# ProPrj_ESP32-CNC_2025-08-15.net
KiCad netlist of a schematic drawn in EasyEDA Pro
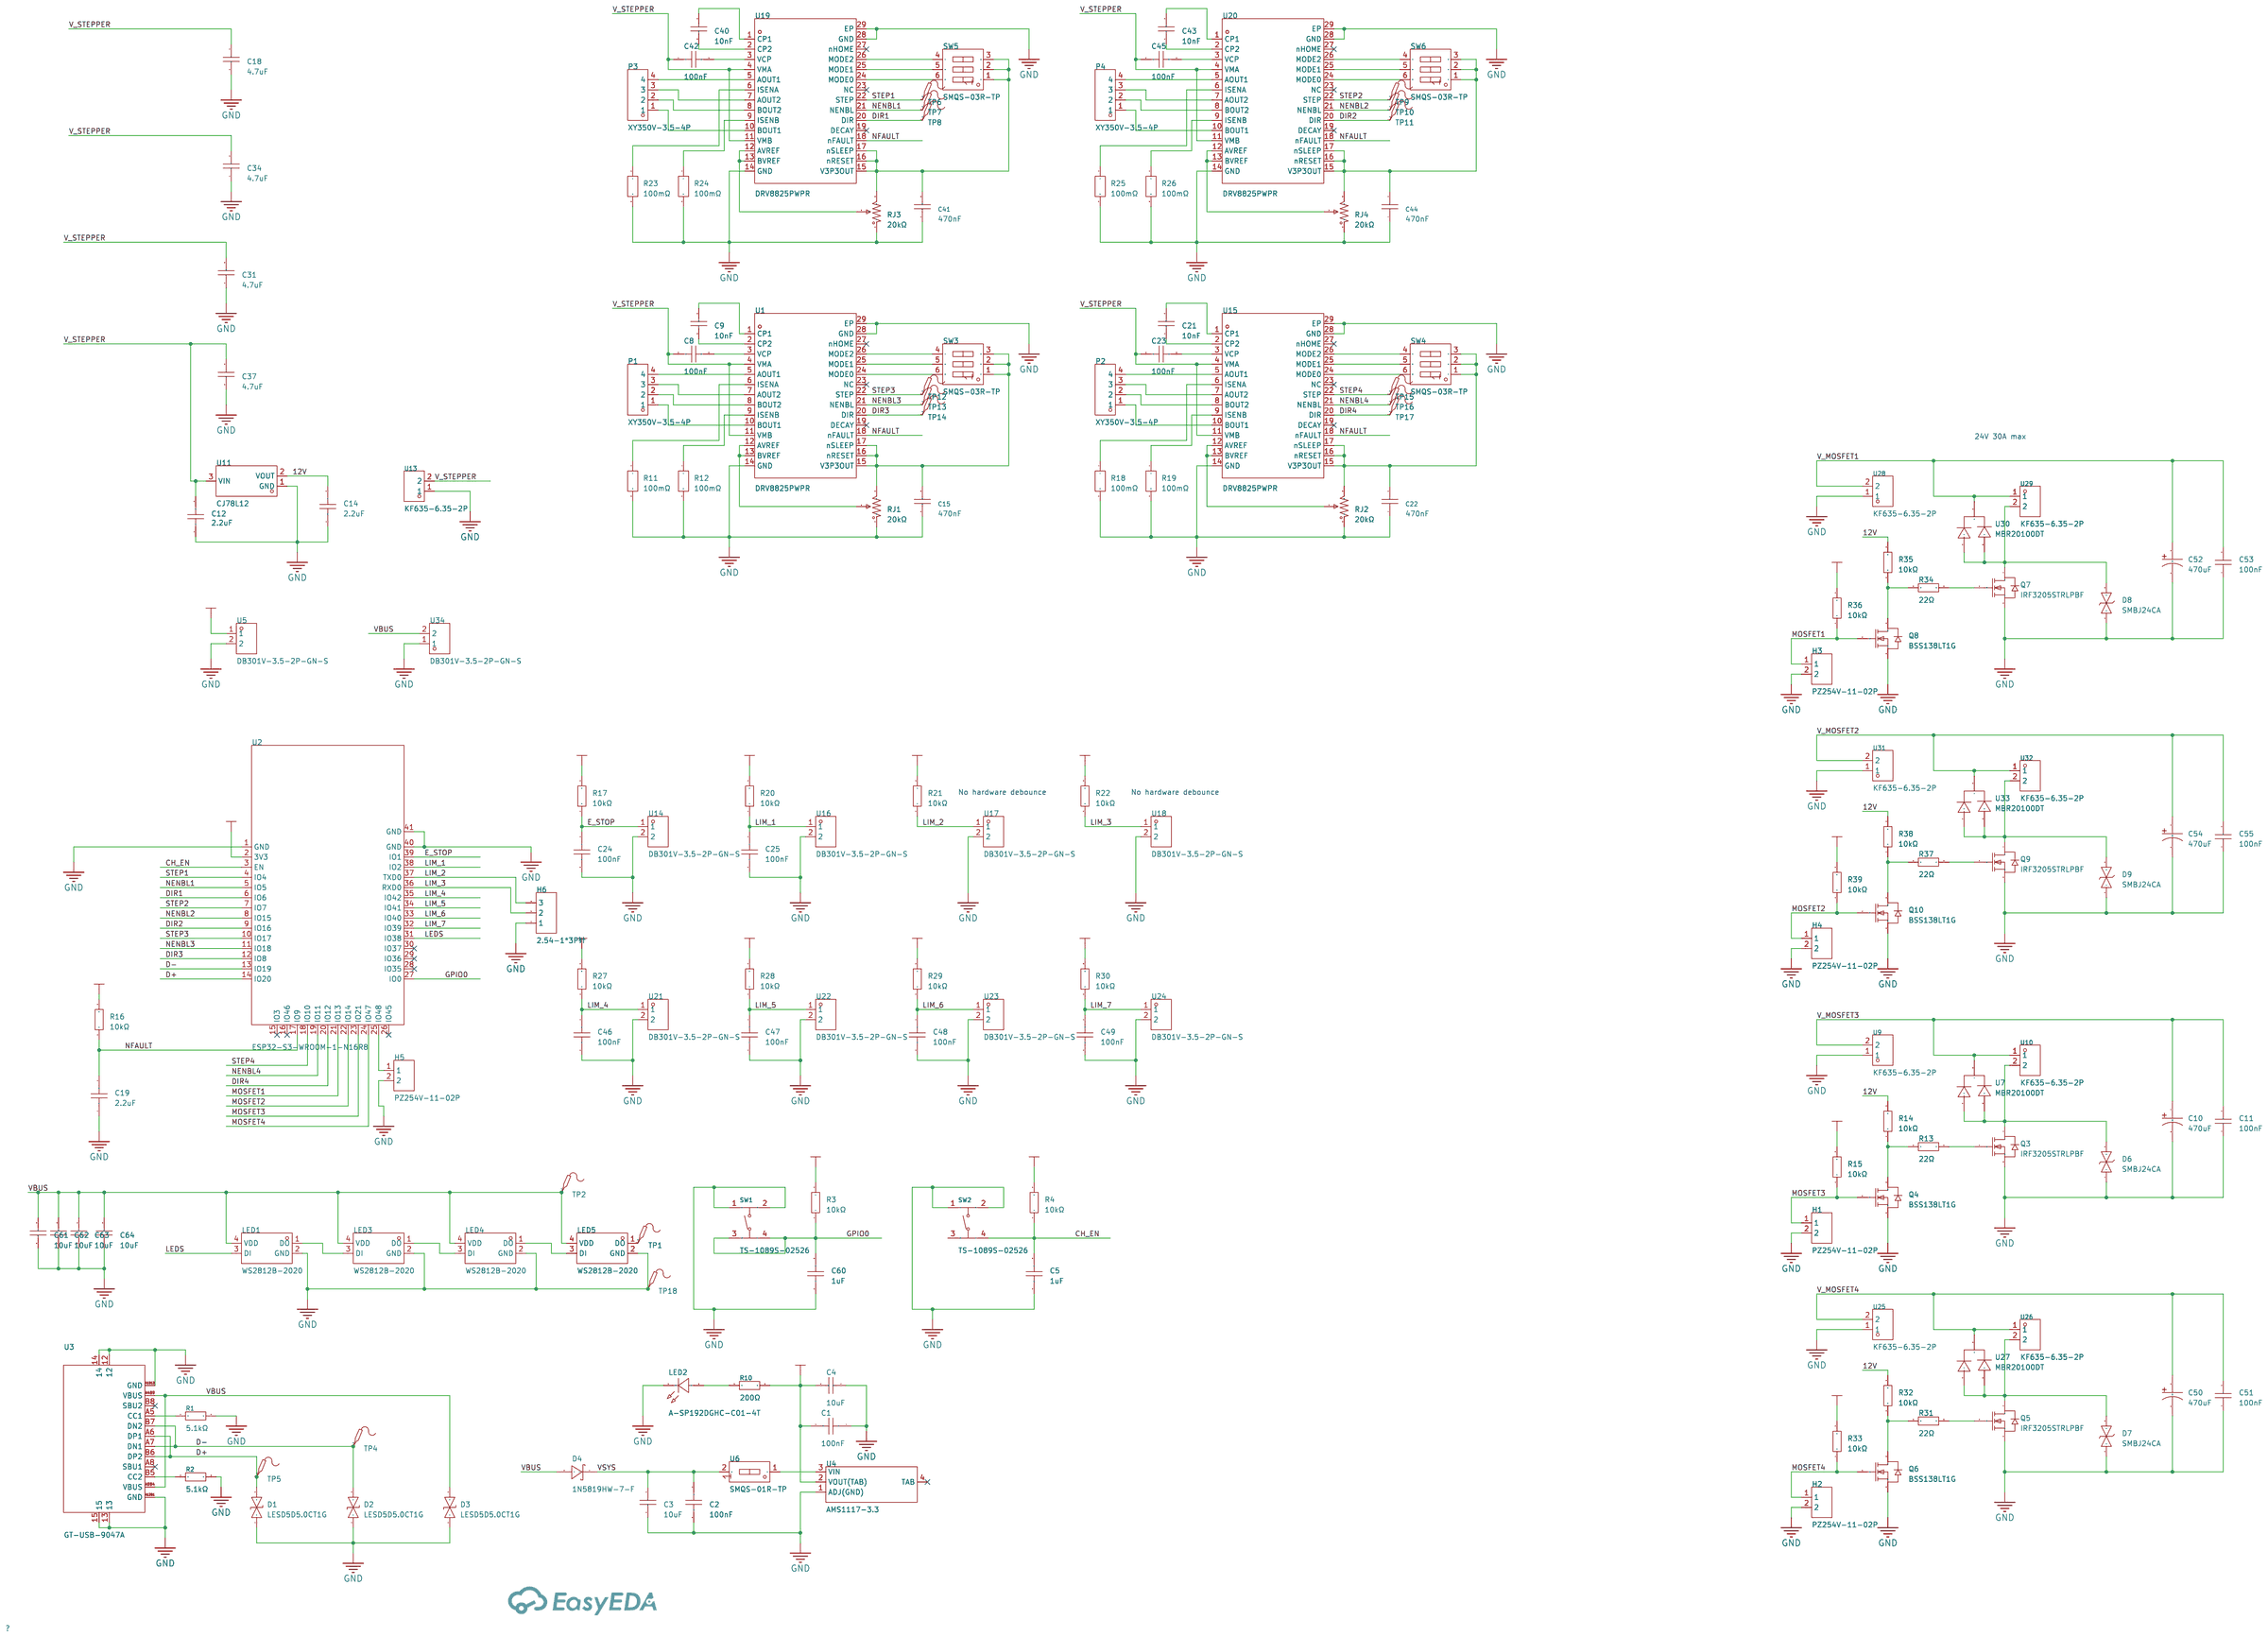
[diagram p0: schematic sheet]

(export (version "E")
  (design (tool "Eeschema 10.0.6"))
  (components
    (comp (ref "C1")
      (value "100nF")
      (footprint "easyedapro:C0402")
      (fields
        (field (name "Manufacturer Part") "CL21B104KCFNNNE")
        (field (name "Manufacturer") "SAMSUNG(三星)")
      )
      (libsource (lib "easyedapro") (part "CL05B104KO5NNNC"))
    )
    (comp (ref "C2")
      (value "100nF")
      (footprint "easyedapro:C0402")
      (fields
        (field (name "Manufacturer Part") "CL21B104KCFNNNE")
        (field (name "Manufacturer") "SAMSUNG(三星)")
      )
      (libsource (lib "easyedapro") (part "CL05B104KO5NNNC"))
    )
    (comp (ref "C3")
      (value "10uF")
      (footprint "easyedapro:C0402")
      (fields
        (field (name "Manufacturer Part") "CL05A106MQ5NUNC")
        (field (name "Manufacturer") "SAMSUNG(三星)")
      )
      (libsource (lib "easyedapro") (part "CL05A106MQ5NUNC"))
    )
    (comp (ref "C4")
      (value "10uF")
      (footprint "easyedapro:C0402")
      (fields
        (field (name "Manufacturer Part") "CL05A106MQ5NUNC")
        (field (name "Manufacturer") "SAMSUNG(三星)")
      )
      (libsource (lib "easyedapro") (part "CL05A106MQ5NUNC"))
    )
    (comp (ref "C5")
      (value "1uF")
      (footprint "easyedapro:C0402")
      (fields
        (field (name "Manufacturer Part") "CL05A105KA5NQNC")
        (field (name "Manufacturer") "SAMSUNG(三星)")
      )
      (libsource (lib "easyedapro") (part "CL05A105KA5NQNC"))
    )
    (comp (ref "C8")
      (value "100nF")
      (footprint "easyedapro:C0603")
      (fields
        (field (name "Manufacturer Part") "CL21B104KCFNNNE")
        (field (name "Manufacturer") "SAMSUNG(三星)")
      )
      (libsource (lib "easyedapro") (part "CC0603KRX7R9BB104"))
    )
    (comp (ref "C9")
      (value "10nF")
      (footprint "easyedapro:C0805")
      (fields
        (field (name "Manufacturer Part") "CL21B103KBANNNC")
        (field (name "Manufacturer") "SAMSUNG(三星)")
      )
      (libsource (lib "easyedapro") (part "CL21B103KBANNNC"))
    )
    (comp (ref "C10")
      (value "470uF")
      (footprint "easyedapro:CAP-SMD_BD12.5-L13.0-W13.0-RD")
      (fields (field (name "Manufacturer Part") "RVT1H471M1213") (field (name "Manufacturer") "ROQANG(容强)"))
      (libsource (lib "easyedapro") (part "RVT1H471M1213"))
    )
    (comp (ref "C11")
      (value "100nF")
      (footprint "easyedapro:C0805")
      (fields
        (field (name "Manufacturer Part") "CL21B104KCFNNNE")
        (field (name "Manufacturer") "SAMSUNG(三星)")
      )
      (libsource (lib "easyedapro") (part "CL21B104KCFNNNE"))
    )
    (comp (ref "C12")
      (value "2.2uF")
      (footprint "easyedapro:C0805")
      (fields
        (field (name "Manufacturer Part") "CL21A225KBQNNNE")
        (field (name "Manufacturer") "SAMSUNG(三星)")
      )
      (libsource (lib "easyedapro") (part "CL21A225KBQNNNE"))
    )
    (comp (ref "C14")
      (value "2.2uF")
      (footprint "easyedapro:C0805")
      (fields
        (field (name "Manufacturer Part") "CL21A225KBQNNNE")
        (field (name "Manufacturer") "SAMSUNG(三星)")
      )
      (libsource (lib "easyedapro") (part "CL21A225KBQNNNE"))
    )
    (comp (ref "C15")
      (value "470nF")
      (footprint "easyedapro:C0805")
      (fields
        (field (name "Manufacturer Part") "CL21B474KBFNNNE")
        (field (name "Manufacturer") "SAMSUNG(三星)")
      )
      (libsource (lib "easyedapro") (part "CL21B474KBFNNNE"))
    )
    (comp (ref "C18")
      (value "4.7uF")
      (footprint "easyedapro:C1206")
      (description "Capacitance:4.7uF Tolerance:±10% Tolerance:±10% Voltage Rating:50V Temperature Coefficient:X7R")
      (fields (field (name "Manufacturer Part") "1206B475K500NT") (field (name "Manufacturer") "FH(风华)"))
      (libsource (lib "easyedapro") (part "1206B475K500NT"))
    )
    (comp (ref "C19")
      (value "2.2uF")
      (footprint "easyedapro:C0805")
      (fields
        (field (name "Manufacturer Part") "CL21A225KBQNNNE")
        (field (name "Manufacturer") "SAMSUNG(三星)")
      )
      (libsource (lib "easyedapro") (part "CL21A225KBQNNNE"))
    )
    (comp (ref "C21")
      (value "10nF")
      (footprint "easyedapro:C0805")
      (fields
        (field (name "Manufacturer Part") "CL21B103KBANNNC")
        (field (name "Manufacturer") "SAMSUNG(三星)")
      )
      (libsource (lib "easyedapro") (part "CL21B103KBANNNC"))
    )
    (comp (ref "C22")
      (value "470nF")
      (footprint "easyedapro:C0805")
      (fields
        (field (name "Manufacturer Part") "CL21B474KBFNNNE")
        (field (name "Manufacturer") "SAMSUNG(三星)")
      )
      (libsource (lib "easyedapro") (part "CL21B474KBFNNNE"))
    )
    (comp (ref "C23")
      (value "100nF")
      (footprint "easyedapro:C0603")
      (fields
        (field (name "Manufacturer Part") "CL21B104KCFNNNE")
        (field (name "Manufacturer") "SAMSUNG(三星)")
      )
      (libsource (lib "easyedapro") (part "CC0603KRX7R9BB104"))
    )
    (comp (ref "C24")
      (value "100nF")
      (footprint "easyedapro:C0402")
      (fields
        (field (name "Manufacturer Part") "CL21B104KCFNNNE")
        (field (name "Manufacturer") "SAMSUNG(三星)")
      )
      (libsource (lib "easyedapro") (part "CL05B104KO5NNNC"))
    )
    (comp (ref "C25")
      (value "100nF")
      (footprint "easyedapro:C0402")
      (fields
        (field (name "Manufacturer Part") "CL21B104KCFNNNE")
        (field (name "Manufacturer") "SAMSUNG(三星)")
      )
      (libsource (lib "easyedapro") (part "CL05B104KO5NNNC"))
    )
    (comp (ref "C31")
      (value "4.7uF")
      (footprint "easyedapro:C1206")
      (description "Capacitance:4.7uF Tolerance:±10% Tolerance:±10% Voltage Rating:50V Temperature Coefficient:X7R")
      (fields (field (name "Manufacturer Part") "1206B475K500NT") (field (name "Manufacturer") "FH(风华)"))
      (libsource (lib "easyedapro") (part "1206B475K500NT"))
    )
    (comp (ref "C34")
      (value "4.7uF")
      (footprint "easyedapro:C1206")
      (description "Capacitance:4.7uF Tolerance:±10% Tolerance:±10% Voltage Rating:50V Temperature Coefficient:X7R")
      (fields (field (name "Manufacturer Part") "1206B475K500NT") (field (name "Manufacturer") "FH(风华)"))
      (libsource (lib "easyedapro") (part "1206B475K500NT"))
    )
    (comp (ref "C37")
      (value "4.7uF")
      (footprint "easyedapro:C1206")
      (description "Capacitance:4.7uF Tolerance:±10% Tolerance:±10% Voltage Rating:50V Temperature Coefficient:X7R")
      (fields (field (name "Manufacturer Part") "1206B475K500NT") (field (name "Manufacturer") "FH(风华)"))
      (libsource (lib "easyedapro") (part "1206B475K500NT"))
    )
    (comp (ref "C40")
      (value "10nF")
      (footprint "easyedapro:C0805")
      (fields
        (field (name "Manufacturer Part") "CL21B103KBANNNC")
        (field (name "Manufacturer") "SAMSUNG(三星)")
      )
      (libsource (lib "easyedapro") (part "CL21B103KBANNNC"))
    )
    (comp (ref "C41")
      (value "470nF")
      (footprint "easyedapro:C0805")
      (fields
        (field (name "Manufacturer Part") "CL21B474KBFNNNE")
        (field (name "Manufacturer") "SAMSUNG(三星)")
      )
      (libsource (lib "easyedapro") (part "CL21B474KBFNNNE"))
    )
    (comp (ref "C42")
      (value "100nF")
      (footprint "easyedapro:C0603")
      (fields
        (field (name "Manufacturer Part") "CL21B104KCFNNNE")
        (field (name "Manufacturer") "SAMSUNG(三星)")
      )
      (libsource (lib "easyedapro") (part "CC0603KRX7R9BB104"))
    )
    (comp (ref "C43")
      (value "10nF")
      (footprint "easyedapro:C0805")
      (fields
        (field (name "Manufacturer Part") "CL21B103KBANNNC")
        (field (name "Manufacturer") "SAMSUNG(三星)")
      )
      (libsource (lib "easyedapro") (part "CL21B103KBANNNC"))
    )
    (comp (ref "C44")
      (value "470nF")
      (footprint "easyedapro:C0805")
      (fields
        (field (name "Manufacturer Part") "CL21B474KBFNNNE")
        (field (name "Manufacturer") "SAMSUNG(三星)")
      )
      (libsource (lib "easyedapro") (part "CL21B474KBFNNNE"))
    )
    (comp (ref "C45")
      (value "100nF")
      (footprint "easyedapro:C0603")
      (fields
        (field (name "Manufacturer Part") "CL21B104KCFNNNE")
        (field (name "Manufacturer") "SAMSUNG(三星)")
      )
      (libsource (lib "easyedapro") (part "CC0603KRX7R9BB104"))
    )
    (comp (ref "C46")
      (value "100nF")
      (footprint "easyedapro:C0402")
      (fields
        (field (name "Manufacturer Part") "CL21B104KCFNNNE")
        (field (name "Manufacturer") "SAMSUNG(三星)")
      )
      (libsource (lib "easyedapro") (part "CL05B104KO5NNNC"))
    )
    (comp (ref "C47")
      (value "100nF")
      (footprint "easyedapro:C0402")
      (fields
        (field (name "Manufacturer Part") "CL21B104KCFNNNE")
        (field (name "Manufacturer") "SAMSUNG(三星)")
      )
      (libsource (lib "easyedapro") (part "CL05B104KO5NNNC"))
    )
    (comp (ref "C48")
      (value "100nF")
      (footprint "easyedapro:C0402")
      (fields
        (field (name "Manufacturer Part") "CL21B104KCFNNNE")
        (field (name "Manufacturer") "SAMSUNG(三星)")
      )
      (libsource (lib "easyedapro") (part "CL05B104KO5NNNC"))
    )
    (comp (ref "C49")
      (value "100nF")
      (footprint "easyedapro:C0402")
      (fields
        (field (name "Manufacturer Part") "CL21B104KCFNNNE")
        (field (name "Manufacturer") "SAMSUNG(三星)")
      )
      (libsource (lib "easyedapro") (part "CL05B104KO5NNNC"))
    )
    (comp (ref "C50")
      (value "470uF")
      (footprint "easyedapro:CAP-SMD_BD12.5-L13.0-W13.0-RD")
      (fields (field (name "Manufacturer Part") "RVT1H471M1213") (field (name "Manufacturer") "ROQANG(容强)"))
      (libsource (lib "easyedapro") (part "RVT1H471M1213"))
    )
    (comp (ref "C51")
      (value "100nF")
      (footprint "easyedapro:C0805")
      (fields
        (field (name "Manufacturer Part") "CL21B104KCFNNNE")
        (field (name "Manufacturer") "SAMSUNG(三星)")
      )
      (libsource (lib "easyedapro") (part "CL21B104KCFNNNE"))
    )
    (comp (ref "C52")
      (value "470uF")
      (footprint "easyedapro:CAP-SMD_BD12.5-L13.0-W13.0-RD")
      (fields (field (name "Manufacturer Part") "RVT1H471M1213") (field (name "Manufacturer") "ROQANG(容强)"))
      (libsource (lib "easyedapro") (part "RVT1H471M1213"))
    )
    (comp (ref "C53")
      (value "100nF")
      (footprint "easyedapro:C0805")
      (fields
        (field (name "Manufacturer Part") "CL21B104KCFNNNE")
        (field (name "Manufacturer") "SAMSUNG(三星)")
      )
      (libsource (lib "easyedapro") (part "CL21B104KCFNNNE"))
    )
    (comp (ref "C54")
      (value "470uF")
      (footprint "easyedapro:CAP-SMD_BD12.5-L13.0-W13.0-RD")
      (fields (field (name "Manufacturer Part") "RVT1H471M1213") (field (name "Manufacturer") "ROQANG(容强)"))
      (libsource (lib "easyedapro") (part "RVT1H471M1213"))
    )
    (comp (ref "C55")
      (value "100nF")
      (footprint "easyedapro:C0805")
      (fields
        (field (name "Manufacturer Part") "CL21B104KCFNNNE")
        (field (name "Manufacturer") "SAMSUNG(三星)")
      )
      (libsource (lib "easyedapro") (part "CL21B104KCFNNNE"))
    )
    (comp (ref "C60")
      (value "1uF")
      (footprint "easyedapro:C0402")
      (fields
        (field (name "Manufacturer Part") "CL05A105KA5NQNC")
        (field (name "Manufacturer") "SAMSUNG(三星)")
      )
      (libsource (lib "easyedapro") (part "CL05A105KA5NQNC"))
    )
    (comp (ref "C61")
      (value "10uF")
      (footprint "easyedapro:C0402")
      (fields
        (field (name "Manufacturer Part") "CL05A106MQ5NUNC")
        (field (name "Manufacturer") "SAMSUNG(三星)")
      )
      (libsource (lib "easyedapro") (part "CL05A106MQ5NUNC"))
    )
    (comp (ref "C62")
      (value "10uF")
      (footprint "easyedapro:C0402")
      (fields
        (field (name "Manufacturer Part") "CL05A106MQ5NUNC")
        (field (name "Manufacturer") "SAMSUNG(三星)")
      )
      (libsource (lib "easyedapro") (part "CL05A106MQ5NUNC"))
    )
    (comp (ref "C63")
      (value "10uF")
      (footprint "easyedapro:C0402")
      (fields
        (field (name "Manufacturer Part") "CL05A106MQ5NUNC")
        (field (name "Manufacturer") "SAMSUNG(三星)")
      )
      (libsource (lib "easyedapro") (part "CL05A106MQ5NUNC"))
    )
    (comp (ref "C64")
      (value "10uF")
      (footprint "easyedapro:C0402")
      (fields
        (field (name "Manufacturer Part") "CL05A106MQ5NUNC")
        (field (name "Manufacturer") "SAMSUNG(三星)")
      )
      (libsource (lib "easyedapro") (part "CL05A106MQ5NUNC"))
    )
    (comp (ref "D1")
      (value "LESD5D5.0CT1G")
      (footprint "easyedapro:SOD-523_L1.2-W0.8-LS1.6-BI")
      (fields (field (name "Manufacturer") "LRC(乐山无线电)"))
      (libsource (lib "easyedapro") (part "LESD5D5.0CT1G"))
    )
    (comp (ref "D2")
      (value "LESD5D5.0CT1G")
      (footprint "easyedapro:SOD-523_L1.2-W0.8-LS1.6-BI")
      (fields (field (name "Manufacturer") "LRC(乐山无线电)"))
      (libsource (lib "easyedapro") (part "LESD5D5.0CT1G"))
    )
    (comp (ref "D3")
      (value "LESD5D5.0CT1G")
      (footprint "easyedapro:SOD-523_L1.2-W0.8-LS1.6-BI")
      (fields (field (name "Manufacturer") "LRC(乐山无线电)"))
      (libsource (lib "easyedapro") (part "LESD5D5.0CT1G"))
    )
    (comp (ref "D4")
      (value "1N5819HW-7-F")
      (footprint "easyedapro:SOD-123_L2.7-W1.6-LS3.7-RD")
      (fields (field (name "Manufacturer") "DIODES(美台)"))
      (libsource (lib "easyedapro") (part "1N5819HW-7-F"))
    )
    (comp (ref "D6")
      (value "SMBJ24CA")
      (footprint "easyedapro:SMBG_L4.3-W3.6-LS6.2-BI")
      (fields (field (name "Manufacturer") "JUXING(钜兴)"))
      (libsource (lib "easyedapro") (part "SMBJ24CA_C19634091"))
    )
    (comp (ref "D7")
      (value "SMBJ24CA")
      (footprint "easyedapro:SMBG_L4.3-W3.6-LS6.2-BI")
      (fields (field (name "Manufacturer") "JUXING(钜兴)"))
      (libsource (lib "easyedapro") (part "SMBJ24CA_C19634091"))
    )
    (comp (ref "D8")
      (value "SMBJ24CA")
      (footprint "easyedapro:SMBG_L4.3-W3.6-LS6.2-BI")
      (fields (field (name "Manufacturer") "JUXING(钜兴)"))
      (libsource (lib "easyedapro") (part "SMBJ24CA_C19634091"))
    )
    (comp (ref "D9")
      (value "SMBJ24CA")
      (footprint "easyedapro:SMBG_L4.3-W3.6-LS6.2-BI")
      (fields (field (name "Manufacturer") "JUXING(钜兴)"))
      (libsource (lib "easyedapro") (part "SMBJ24CA_C19634091"))
    )
    (comp (ref "H1")
      (value "PZ254V-11-02P")
      (footprint "easyedapro:HDR-TH_2P-P2.54-V-M")
      (fields (field (name "Manufacturer") "XFCN(兴飞)"))
      (libsource (lib "easyedapro") (part "PZ254V-11-02P"))
    )
    (comp (ref "H2")
      (value "PZ254V-11-02P")
      (footprint "easyedapro:HDR-TH_2P-P2.54-V-M")
      (fields (field (name "Manufacturer") "XFCN(兴飞)"))
      (libsource (lib "easyedapro") (part "PZ254V-11-02P"))
    )
    (comp (ref "H3")
      (value "PZ254V-11-02P")
      (footprint "easyedapro:HDR-TH_2P-P2.54-V-M")
      (fields (field (name "Manufacturer") "XFCN(兴飞)"))
      (libsource (lib "easyedapro") (part "PZ254V-11-02P"))
    )
    (comp (ref "H4")
      (value "PZ254V-11-02P")
      (footprint "easyedapro:HDR-TH_2P-P2.54-V-M")
      (fields (field (name "Manufacturer") "XFCN(兴飞)"))
      (libsource (lib "easyedapro") (part "PZ254V-11-02P"))
    )
    (comp (ref "H5")
      (value "PZ254V-11-02P")
      (footprint "easyedapro:HDR-TH_2P-P2.54-V-M")
      (fields (field (name "Manufacturer") "XFCN(兴飞)"))
      (libsource (lib "easyedapro") (part "PZ254V-11-02P"))
    )
    (comp (ref "H6")
      (value "2.54-1*3P针")
      (footprint "easyedapro:HDR-TH_3P-P2.54-V-M-1")
      (fields (field (name "Manufacturer") "BOOMELE(博穆精密)"))
      (libsource (lib "easyedapro") (part "Header-Male-2.54_1x3"))
    )
    (comp (ref "LED1")
      (value "WS2812B-2020")
      (footprint "easyedapro:LED-SMD_4P-L2.0-W2.0-TL_WS2812B-2020")
      (fields (field (name "Manufacturer") "worldsemi"))
      (libsource (lib "easyedapro") (part "WS2812B-2020"))
    )
    (comp (ref "LED2")
      (value "A-SP192DGHC-C01-4T")
      (footprint "easyedapro:LED0603-FD")
      (fields (field (name "Manufacturer") "Amicc(欧密格光电)"))
      (libsource (lib "easyedapro") (part "A-SP192DGHC-C01-4T"))
    )
    (comp (ref "LED3")
      (value "WS2812B-2020")
      (footprint "easyedapro:LED-SMD_4P-L2.0-W2.0-TL_WS2812B-2020")
      (fields (field (name "Manufacturer") "worldsemi"))
      (libsource (lib "easyedapro") (part "WS2812B-2020"))
    )
    (comp (ref "LED4")
      (value "WS2812B-2020")
      (footprint "easyedapro:LED-SMD_4P-L2.0-W2.0-TL_WS2812B-2020")
      (fields (field (name "Manufacturer") "worldsemi"))
      (libsource (lib "easyedapro") (part "WS2812B-2020"))
    )
    (comp (ref "LED5")
      (value "WS2812B-2020")
      (footprint "easyedapro:LED-SMD_4P-L2.0-W2.0-TL_WS2812B-2020")
      (fields (field (name "Manufacturer") "worldsemi"))
      (libsource (lib "easyedapro") (part "WS2812B-2020"))
    )
    (comp (ref "P1")
      (value "XY350V-3.5-4P")
      (footprint "easyedapro:CONN-TH_XY350V-3.5-4P")
      (fields (field (name "Manufacturer") "XINLAIYA(新莱亚)"))
      (libsource (lib "easyedapro") (part "XY350V-3.5-4P"))
    )
    (comp (ref "P2")
      (value "XY350V-3.5-4P")
      (footprint "easyedapro:CONN-TH_XY350V-3.5-4P")
      (fields (field (name "Manufacturer") "XINLAIYA(新莱亚)"))
      (libsource (lib "easyedapro") (part "XY350V-3.5-4P"))
    )
    (comp (ref "P3")
      (value "XY350V-3.5-4P")
      (footprint "easyedapro:CONN-TH_XY350V-3.5-4P")
      (fields (field (name "Manufacturer") "XINLAIYA(新莱亚)"))
      (libsource (lib "easyedapro") (part "XY350V-3.5-4P"))
    )
    (comp (ref "P4")
      (value "XY350V-3.5-4P")
      (footprint "easyedapro:CONN-TH_XY350V-3.5-4P")
      (fields (field (name "Manufacturer") "XINLAIYA(新莱亚)"))
      (libsource (lib "easyedapro") (part "XY350V-3.5-4P"))
    )
    (comp (ref "Q3")
      (value "IRF3205STRLPBF")
      (footprint "easyedapro:TO-263-2_L10.0-W9.1-P5.08-LS15.2-TL")
      (fields (field (name "Manufacturer") "Infineon(英飞凌)"))
      (libsource (lib "easyedapro") (part "IRF3205STRLPBF"))
    )
    (comp (ref "Q4")
      (value "BSS138LT1G")
      (footprint "easyedapro:SOT-23-3_L2.9-W1.6-P1.90-LS2.8-BR")
      (fields (field (name "Manufacturer") "onsemi(安森美)"))
      (libsource (lib "easyedapro") (part "BSS138LT1G"))
    )
    (comp (ref "Q5")
      (value "IRF3205STRLPBF")
      (footprint "easyedapro:TO-263-2_L10.0-W9.1-P5.08-LS15.2-TL")
      (fields (field (name "Manufacturer") "Infineon(英飞凌)"))
      (libsource (lib "easyedapro") (part "IRF3205STRLPBF"))
    )
    (comp (ref "Q6")
      (value "BSS138LT1G")
      (footprint "easyedapro:SOT-23-3_L2.9-W1.6-P1.90-LS2.8-BR")
      (fields (field (name "Manufacturer") "onsemi(安森美)"))
      (libsource (lib "easyedapro") (part "BSS138LT1G"))
    )
    (comp (ref "Q7")
      (value "IRF3205STRLPBF")
      (footprint "easyedapro:TO-263-2_L10.0-W9.1-P5.08-LS15.2-TL")
      (fields (field (name "Manufacturer") "Infineon(英飞凌)"))
      (libsource (lib "easyedapro") (part "IRF3205STRLPBF"))
    )
    (comp (ref "Q8")
      (value "BSS138LT1G")
      (footprint "easyedapro:SOT-23-3_L2.9-W1.6-P1.90-LS2.8-BR")
      (fields (field (name "Manufacturer") "onsemi(安森美)"))
      (libsource (lib "easyedapro") (part "BSS138LT1G"))
    )
    (comp (ref "Q9")
      (value "IRF3205STRLPBF")
      (footprint "easyedapro:TO-263-2_L10.0-W9.1-P5.08-LS15.2-TL")
      (fields (field (name "Manufacturer") "Infineon(英飞凌)"))
      (libsource (lib "easyedapro") (part "IRF3205STRLPBF"))
    )
    (comp (ref "Q10")
      (value "BSS138LT1G")
      (footprint "easyedapro:SOT-23-3_L2.9-W1.6-P1.90-LS2.8-BR")
      (fields (field (name "Manufacturer") "onsemi(安森美)"))
      (libsource (lib "easyedapro") (part "BSS138LT1G"))
    )
    (comp (ref "R1")
      (value "5.1kΩ")
      (footprint "easyedapro:R0402")
      (fields
        (field (name "Manufacturer Part") "0402WGF5101TCE")
        (field (name "Manufacturer") "UNI-ROYAL(厚声)")
      )
      (libsource (lib "easyedapro") (part "0402WGF5101TCE"))
    )
    (comp (ref "R2")
      (value "5.1kΩ")
      (footprint "easyedapro:R0402")
      (fields
        (field (name "Manufacturer Part") "0402WGF5101TCE")
        (field (name "Manufacturer") "UNI-ROYAL(厚声)")
      )
      (libsource (lib "easyedapro") (part "0402WGF5101TCE"))
    )
    (comp (ref "R3")
      (value "10kΩ")
      (footprint "easyedapro:R0402")
      (fields
        (field (name "Manufacturer Part") "0402WGF1002TCE")
        (field (name "Manufacturer") "UNI-ROYAL(厚声)")
      )
      (libsource (lib "easyedapro") (part "0402WGF1002TCE"))
    )
    (comp (ref "R4")
      (value "10kΩ")
      (footprint "easyedapro:R0402")
      (fields
        (field (name "Manufacturer Part") "0402WGF1002TCE")
        (field (name "Manufacturer") "UNI-ROYAL(厚声)")
      )
      (libsource (lib "easyedapro") (part "0402WGF1002TCE"))
    )
    (comp (ref "R10")
      (value "200Ω")
      (footprint "easyedapro:R0402")
      (fields
        (field (name "Manufacturer Part") "0402WGF2000TCE")
        (field (name "Manufacturer") "UNI-ROYAL(厚声)")
      )
      (libsource (lib "easyedapro") (part "0402WGF2000TCE"))
    )
    (comp (ref "R11")
      (value "100mΩ")
      (footprint "easyedapro:R1206")
      (fields
        (field (name "Manufacturer Part") "HoYH1206-1W-100mR-1%")
        (field (name "Manufacturer") "Milliohm(毫欧)")
      )
      (libsource (lib "easyedapro") (part "HOYH1206-1W-100MR-1%"))
    )
    (comp (ref "R12")
      (value "100mΩ")
      (footprint "easyedapro:R1206")
      (fields
        (field (name "Manufacturer Part") "HoYH1206-1W-100mR-1%")
        (field (name "Manufacturer") "Milliohm(毫欧)")
      )
      (libsource (lib "easyedapro") (part "HOYH1206-1W-100MR-1%"))
    )
    (comp (ref "R13")
      (value "22Ω")
      (footprint "easyedapro:R0603")
      (fields
        (field (name "Manufacturer Part") "0603WAF220JT5E")
        (field (name "Manufacturer") "UNI-ROYAL(厚声)")
      )
      (libsource (lib "easyedapro") (part "0603WAF220JT5E"))
    )
    (comp (ref "R14")
      (value "10kΩ")
      (footprint "easyedapro:R0402")
      (fields
        (field (name "Manufacturer Part") "0402WGF1002TCE")
        (field (name "Manufacturer") "UNI-ROYAL(厚声)")
      )
      (libsource (lib "easyedapro") (part "0402WGF1002TCE"))
    )
    (comp (ref "R15")
      (value "10kΩ")
      (footprint "easyedapro:R0402")
      (fields
        (field (name "Manufacturer Part") "0402WGF1002TCE")
        (field (name "Manufacturer") "UNI-ROYAL(厚声)")
      )
      (libsource (lib "easyedapro") (part "0402WGF1002TCE"))
    )
    (comp (ref "R16")
      (value "10kΩ")
      (footprint "easyedapro:R0402")
      (fields
        (field (name "Manufacturer Part") "0402WGF1002TCE")
        (field (name "Manufacturer") "UNI-ROYAL(厚声)")
      )
      (libsource (lib "easyedapro") (part "0402WGF1002TCE"))
    )
    (comp (ref "R17")
      (value "10kΩ")
      (footprint "easyedapro:R0402")
      (fields
        (field (name "Manufacturer Part") "0402WGF1002TCE")
        (field (name "Manufacturer") "UNI-ROYAL(厚声)")
      )
      (libsource (lib "easyedapro") (part "0402WGF1002TCE"))
    )
    (comp (ref "R18")
      (value "100mΩ")
      (footprint "easyedapro:R1206")
      (fields
        (field (name "Manufacturer Part") "HoYH1206-1W-100mR-1%")
        (field (name "Manufacturer") "Milliohm(毫欧)")
      )
      (libsource (lib "easyedapro") (part "HOYH1206-1W-100MR-1%"))
    )
    (comp (ref "R19")
      (value "100mΩ")
      (footprint "easyedapro:R1206")
      (fields
        (field (name "Manufacturer Part") "HoYH1206-1W-100mR-1%")
        (field (name "Manufacturer") "Milliohm(毫欧)")
      )
      (libsource (lib "easyedapro") (part "HOYH1206-1W-100MR-1%"))
    )
    (comp (ref "R20")
      (value "10kΩ")
      (footprint "easyedapro:R0402")
      (fields
        (field (name "Manufacturer Part") "0402WGF1002TCE")
        (field (name "Manufacturer") "UNI-ROYAL(厚声)")
      )
      (libsource (lib "easyedapro") (part "0402WGF1002TCE"))
    )
    (comp (ref "R21")
      (value "10kΩ")
      (footprint "easyedapro:R0402")
      (fields
        (field (name "Manufacturer Part") "0402WGF1002TCE")
        (field (name "Manufacturer") "UNI-ROYAL(厚声)")
      )
      (libsource (lib "easyedapro") (part "0402WGF1002TCE"))
    )
    (comp (ref "R22")
      (value "10kΩ")
      (footprint "easyedapro:R0402")
      (fields
        (field (name "Manufacturer Part") "0402WGF1002TCE")
        (field (name "Manufacturer") "UNI-ROYAL(厚声)")
      )
      (libsource (lib "easyedapro") (part "0402WGF1002TCE"))
    )
    (comp (ref "R23")
      (value "100mΩ")
      (footprint "easyedapro:R1206")
      (fields
        (field (name "Manufacturer Part") "HoYH1206-1W-100mR-1%")
        (field (name "Manufacturer") "Milliohm(毫欧)")
      )
      (libsource (lib "easyedapro") (part "HOYH1206-1W-100MR-1%"))
    )
    (comp (ref "R24")
      (value "100mΩ")
      (footprint "easyedapro:R1206")
      (fields
        (field (name "Manufacturer Part") "HoYH1206-1W-100mR-1%")
        (field (name "Manufacturer") "Milliohm(毫欧)")
      )
      (libsource (lib "easyedapro") (part "HOYH1206-1W-100MR-1%"))
    )
    (comp (ref "R25")
      (value "100mΩ")
      (footprint "easyedapro:R1206")
      (fields
        (field (name "Manufacturer Part") "HoYH1206-1W-100mR-1%")
        (field (name "Manufacturer") "Milliohm(毫欧)")
      )
      (libsource (lib "easyedapro") (part "HOYH1206-1W-100MR-1%"))
    )
    (comp (ref "R26")
      (value "100mΩ")
      (footprint "easyedapro:R1206")
      (fields
        (field (name "Manufacturer Part") "HoYH1206-1W-100mR-1%")
        (field (name "Manufacturer") "Milliohm(毫欧)")
      )
      (libsource (lib "easyedapro") (part "HOYH1206-1W-100MR-1%"))
    )
    (comp (ref "R27")
      (value "10kΩ")
      (footprint "easyedapro:R0402")
      (fields
        (field (name "Manufacturer Part") "0402WGF1002TCE")
        (field (name "Manufacturer") "UNI-ROYAL(厚声)")
      )
      (libsource (lib "easyedapro") (part "0402WGF1002TCE"))
    )
    (comp (ref "R28")
      (value "10kΩ")
      (footprint "easyedapro:R0402")
      (fields
        (field (name "Manufacturer Part") "0402WGF1002TCE")
        (field (name "Manufacturer") "UNI-ROYAL(厚声)")
      )
      (libsource (lib "easyedapro") (part "0402WGF1002TCE"))
    )
    (comp (ref "R29")
      (value "10kΩ")
      (footprint "easyedapro:R0402")
      (fields
        (field (name "Manufacturer Part") "0402WGF1002TCE")
        (field (name "Manufacturer") "UNI-ROYAL(厚声)")
      )
      (libsource (lib "easyedapro") (part "0402WGF1002TCE"))
    )
    (comp (ref "R30")
      (value "10kΩ")
      (footprint "easyedapro:R0402")
      (fields
        (field (name "Manufacturer Part") "0402WGF1002TCE")
        (field (name "Manufacturer") "UNI-ROYAL(厚声)")
      )
      (libsource (lib "easyedapro") (part "0402WGF1002TCE"))
    )
    (comp (ref "R31")
      (value "22Ω")
      (footprint "easyedapro:R0603")
      (fields
        (field (name "Manufacturer Part") "0603WAF220JT5E")
        (field (name "Manufacturer") "UNI-ROYAL(厚声)")
      )
      (libsource (lib "easyedapro") (part "0603WAF220JT5E"))
    )
    (comp (ref "R32")
      (value "10kΩ")
      (footprint "easyedapro:R0402")
      (fields
        (field (name "Manufacturer Part") "0402WGF1002TCE")
        (field (name "Manufacturer") "UNI-ROYAL(厚声)")
      )
      (libsource (lib "easyedapro") (part "0402WGF1002TCE"))
    )
    (comp (ref "R33")
      (value "10kΩ")
      (footprint "easyedapro:R0402")
      (fields
        (field (name "Manufacturer Part") "0402WGF1002TCE")
        (field (name "Manufacturer") "UNI-ROYAL(厚声)")
      )
      (libsource (lib "easyedapro") (part "0402WGF1002TCE"))
    )
    (comp (ref "R34")
      (value "22Ω")
      (footprint "easyedapro:R0603")
      (fields
        (field (name "Manufacturer Part") "0603WAF220JT5E")
        (field (name "Manufacturer") "UNI-ROYAL(厚声)")
      )
      (libsource (lib "easyedapro") (part "0603WAF220JT5E"))
    )
    (comp (ref "R35")
      (value "10kΩ")
      (footprint "easyedapro:R0402")
      (fields
        (field (name "Manufacturer Part") "0402WGF1002TCE")
        (field (name "Manufacturer") "UNI-ROYAL(厚声)")
      )
      (libsource (lib "easyedapro") (part "0402WGF1002TCE"))
    )
    (comp (ref "R36")
      (value "10kΩ")
      (footprint "easyedapro:R0402")
      (fields
        (field (name "Manufacturer Part") "0402WGF1002TCE")
        (field (name "Manufacturer") "UNI-ROYAL(厚声)")
      )
      (libsource (lib "easyedapro") (part "0402WGF1002TCE"))
    )
    (comp (ref "R37")
      (value "22Ω")
      (footprint "easyedapro:R0603")
      (fields
        (field (name "Manufacturer Part") "0603WAF220JT5E")
        (field (name "Manufacturer") "UNI-ROYAL(厚声)")
      )
      (libsource (lib "easyedapro") (part "0603WAF220JT5E"))
    )
    (comp (ref "R38")
      (value "10kΩ")
      (footprint "easyedapro:R0402")
      (fields
        (field (name "Manufacturer Part") "0402WGF1002TCE")
        (field (name "Manufacturer") "UNI-ROYAL(厚声)")
      )
      (libsource (lib "easyedapro") (part "0402WGF1002TCE"))
    )
    (comp (ref "R39")
      (value "10kΩ")
      (footprint "easyedapro:R0402")
      (fields
        (field (name "Manufacturer Part") "0402WGF1002TCE")
        (field (name "Manufacturer") "UNI-ROYAL(厚声)")
      )
      (libsource (lib "easyedapro") (part "0402WGF1002TCE"))
    )
    (comp (ref "RJ1")
      (value "20kΩ")
      (footprint "easyedapro:RES-ADJ-SMD_TC33X-2-104E")
      (fields (field (name "Manufacturer Part") "TC33X-2-203E") (field (name "Manufacturer") "BOURNS"))
      (libsource (lib "easyedapro") (part "TC33X-2-203E"))
    )
    (comp (ref "RJ2")
      (value "20kΩ")
      (footprint "easyedapro:RES-ADJ-SMD_TC33X-2-104E")
      (fields (field (name "Manufacturer Part") "TC33X-2-203E") (field (name "Manufacturer") "BOURNS"))
      (libsource (lib "easyedapro") (part "TC33X-2-203E"))
    )
    (comp (ref "RJ3")
      (value "20kΩ")
      (footprint "easyedapro:RES-ADJ-SMD_TC33X-2-104E")
      (fields (field (name "Manufacturer Part") "TC33X-2-203E") (field (name "Manufacturer") "BOURNS"))
      (libsource (lib "easyedapro") (part "TC33X-2-203E"))
    )
    (comp (ref "RJ4")
      (value "20kΩ")
      (footprint "easyedapro:RES-ADJ-SMD_TC33X-2-104E")
      (fields (field (name "Manufacturer Part") "TC33X-2-203E") (field (name "Manufacturer") "BOURNS"))
      (libsource (lib "easyedapro") (part "TC33X-2-203E"))
    )
    (comp (ref "SW1")
      (value "TS-1089S-02526")
      (footprint "easyedapro:SW-SMD_4P-L4.2-W3.3-P2.15-LS5.1")
      (fields (field (name "Manufacturer") "XUNPU(讯普)"))
      (libsource (lib "easyedapro") (part "TS-1089S-02526"))
    )
    (comp (ref "SW2")
      (value "TS-1089S-02526")
      (footprint "easyedapro:SW-SMD_4P-L4.2-W3.3-P2.15-LS5.1")
      (fields (field (name "Manufacturer") "XUNPU(讯普)"))
      (libsource (lib "easyedapro") (part "TS-1089S-02526"))
    )
    (comp (ref "SW3")
      (value "SMQS-03R-TP")
      (footprint "easyedapro:SW-TH_SMQS-03B-TP")
      (fields (field (name "Manufacturer") "SM Switch"))
      (libsource (lib "easyedapro") (part "SMQS-03R-TP"))
    )
    (comp (ref "SW4")
      (value "SMQS-03R-TP")
      (footprint "easyedapro:SW-TH_SMQS-03B-TP")
      (fields (field (name "Manufacturer") "SM Switch"))
      (libsource (lib "easyedapro") (part "SMQS-03R-TP"))
    )
    (comp (ref "SW5")
      (value "SMQS-03R-TP")
      (footprint "easyedapro:SW-TH_SMQS-03B-TP")
      (fields (field (name "Manufacturer") "SM Switch"))
      (libsource (lib "easyedapro") (part "SMQS-03R-TP"))
    )
    (comp (ref "SW6")
      (value "SMQS-03R-TP")
      (footprint "easyedapro:SW-TH_SMQS-03B-TP")
      (fields (field (name "Manufacturer") "SM Switch"))
      (libsource (lib "easyedapro") (part "SMQS-03R-TP"))
    )
    (comp (ref "TP1")
      (value "~")
      (footprint "easyedapro:Test-Point-0.5mm")
      (description "Test Point 测试点")
      (libsource (lib "easyedapro") (part "Test-Point"))
    )
    (comp (ref "TP2")
      (value "~")
      (footprint "easyedapro:Test-Point-0.5mm")
      (description "Test Point 测试点")
      (libsource (lib "easyedapro") (part "Test-Point"))
    )
    (comp (ref "TP4")
      (value "~")
      (footprint "easyedapro:Test-Point-0.5mm")
      (description "Test Point 测试点")
      (libsource (lib "easyedapro") (part "Test-Point"))
    )
    (comp (ref "TP5")
      (value "~")
      (footprint "easyedapro:Test-Point-0.5mm")
      (description "Test Point 测试点")
      (libsource (lib "easyedapro") (part "Test-Point"))
    )
    (comp (ref "TP6")
      (value "~")
      (footprint "easyedapro:Test-Point-0.5mm")
      (description "Test Point 测试点")
      (libsource (lib "easyedapro") (part "Test-Point"))
    )
    (comp (ref "TP7")
      (value "~")
      (footprint "easyedapro:Test-Point-0.5mm")
      (description "Test Point 测试点")
      (libsource (lib "easyedapro") (part "Test-Point"))
    )
    (comp (ref "TP8")
      (value "~")
      (footprint "easyedapro:Test-Point-0.5mm")
      (description "Test Point 测试点")
      (libsource (lib "easyedapro") (part "Test-Point"))
    )
    (comp (ref "TP9")
      (value "~")
      (footprint "easyedapro:Test-Point-0.5mm")
      (description "Test Point 测试点")
      (libsource (lib "easyedapro") (part "Test-Point"))
    )
    (comp (ref "TP10")
      (value "~")
      (footprint "easyedapro:Test-Point-0.5mm")
      (description "Test Point 测试点")
      (libsource (lib "easyedapro") (part "Test-Point"))
    )
    (comp (ref "TP11")
      (value "~")
      (footprint "easyedapro:Test-Point-0.5mm")
      (description "Test Point 测试点")
      (libsource (lib "easyedapro") (part "Test-Point"))
    )
    (comp (ref "TP12")
      (value "~")
      (footprint "easyedapro:Test-Point-0.5mm")
      (description "Test Point 测试点")
      (libsource (lib "easyedapro") (part "Test-Point"))
    )
    (comp (ref "TP13")
      (value "~")
      (footprint "easyedapro:Test-Point-0.5mm")
      (description "Test Point 测试点")
      (libsource (lib "easyedapro") (part "Test-Point"))
    )
    (comp (ref "TP14")
      (value "~")
      (footprint "easyedapro:Test-Point-0.5mm")
      (description "Test Point 测试点")
      (libsource (lib "easyedapro") (part "Test-Point"))
    )
    (comp (ref "TP15")
      (value "~")
      (footprint "easyedapro:Test-Point-0.5mm")
      (description "Test Point 测试点")
      (libsource (lib "easyedapro") (part "Test-Point"))
    )
    (comp (ref "TP16")
      (value "~")
      (footprint "easyedapro:Test-Point-0.5mm")
      (description "Test Point 测试点")
      (libsource (lib "easyedapro") (part "Test-Point"))
    )
    (comp (ref "TP17")
      (value "~")
      (footprint "easyedapro:Test-Point-0.5mm")
      (description "Test Point 测试点")
      (libsource (lib "easyedapro") (part "Test-Point"))
    )
    (comp (ref "TP18")
      (value "~")
      (footprint "easyedapro:Test-Point-0.5mm")
      (description "Test Point 测试点")
      (libsource (lib "easyedapro") (part "Test-Point"))
    )
    (comp (ref "U1")
      (value "DRV8825PWPR")
      (footprint "easyedapro:HTSSOP-28_L9.7-W4.4-P0.65-LS6.4-BL-EP")
      (fields (field (name "Manufacturer") "TI(德州仪器)"))
      (libsource (lib "easyedapro") (part "DRV8825PWPR"))
    )
    (comp (ref "U2")
      (value "ESP32-S3-WROOM-1-N16R8")
      (footprint "easyedapro:WIRELM-SMD_ESP32-S3-WROOM-1")
      (fields (field (name "Manufacturer") "ESPRESSIF(乐鑫)"))
      (libsource (lib "easyedapro") (part "ESP32-S3-WROOM-1(N16R8)"))
    )
    (comp (ref "U3")
      (value "GT-USB-9047A")
      (footprint "easyedapro:USB-C-SMD_GT-USB-9047A")
      (fields (field (name "Manufacturer") "G-Switch(品赞)"))
      (libsource (lib "easyedapro") (part "GT-USB-9047A"))
    )
    (comp (ref "U4")
      (value "AMS1117-3.3")
      (footprint "easyedapro:SOT-223-4_L6.5-W3.5-P2.30-LS7.0-BR")
      (fields (field (name "Manufacturer") "UMW(友台半导体)"))
      (libsource (lib "easyedapro") (part "AMS1117-3.3_C347222"))
    )
    (comp (ref "U5")
      (value "DB301V-3.5-2P-GN-S")
      (footprint "easyedapro:CONN-TH_DB301V-3.5-2P-GN")
      (fields (field (name "Manufacturer") "DORABO(地博电气)"))
      (libsource (lib "easyedapro") (part "DB301V-3.5-2P-GN"))
    )
    (comp (ref "U6")
      (value "SMQS-01R-TP")
      (footprint "easyedapro:SW-TH_KF1001-01P-B0-FL-ON-01B")
      (fields (field (name "Manufacturer") "SM Switch"))
      (libsource (lib "easyedapro") (part "SMQS-01R-TP"))
    )
    (comp (ref "U7")
      (value "MBR20100DT")
      (footprint "easyedapro:TO-252-2_L6.5-W6.1-P4.58-LS10.0-BL")
      (fields (field (name "Manufacturer") "JUXING(钜兴)"))
      (libsource (lib "easyedapro") (part "MBR20100DT_C3011043"))
    )
    (comp (ref "U9")
      (value "KF635-6.35-2P")
      (footprint "easyedapro:CONN-TH_P6.35_KF635-6.35-2P")
      (fields (field (name "Manufacturer") "KEFA(科发)"))
      (libsource (lib "easyedapro") (part "KF635-6.35-2P"))
    )
    (comp (ref "U10")
      (value "KF635-6.35-2P")
      (footprint "easyedapro:CONN-TH_P6.35_KF635-6.35-2P")
      (fields (field (name "Manufacturer") "KEFA(科发)"))
      (libsource (lib "easyedapro") (part "KF635-6.35-2P"))
    )
    (comp (ref "U11")
      (value "CJ78L12")
      (footprint "easyedapro:SOT-23-3L_L2.9-W1.6-P1.90-LS2.8-BL")
      (fields (field (name "Manufacturer") "CJ(江苏长电/长晶)"))
      (libsource (lib "easyedapro") (part "MD7680EC0QA3"))
    )
    (comp (ref "U13")
      (value "KF635-6.35-2P")
      (footprint "easyedapro:CONN-TH_P6.35_KF635-6.35-2P")
      (fields (field (name "Manufacturer") "KEFA(科发)"))
      (libsource (lib "easyedapro") (part "KF635-6.35-2P"))
    )
    (comp (ref "U14")
      (value "DB301V-3.5-2P-GN-S")
      (footprint "easyedapro:CONN-TH_DB301V-3.5-2P-GN")
      (fields (field (name "Manufacturer") "DORABO(地博电气)"))
      (libsource (lib "easyedapro") (part "DB301V-3.5-2P-GN"))
    )
    (comp (ref "U15")
      (value "DRV8825PWPR")
      (footprint "easyedapro:HTSSOP-28_L9.7-W4.4-P0.65-LS6.4-BL-EP")
      (fields (field (name "Manufacturer") "TI(德州仪器)"))
      (libsource (lib "easyedapro") (part "DRV8825PWPR"))
    )
    (comp (ref "U16")
      (value "DB301V-3.5-2P-GN-S")
      (footprint "easyedapro:CONN-TH_DB301V-3.5-2P-GN")
      (fields (field (name "Manufacturer") "DORABO(地博电气)"))
      (libsource (lib "easyedapro") (part "DB301V-3.5-2P-GN"))
    )
    (comp (ref "U17")
      (value "DB301V-3.5-2P-GN-S")
      (footprint "easyedapro:CONN-TH_DB301V-3.5-2P-GN")
      (fields (field (name "Manufacturer") "DORABO(地博电气)"))
      (libsource (lib "easyedapro") (part "DB301V-3.5-2P-GN"))
    )
    (comp (ref "U18")
      (value "DB301V-3.5-2P-GN-S")
      (footprint "easyedapro:CONN-TH_DB301V-3.5-2P-GN")
      (fields (field (name "Manufacturer") "DORABO(地博电气)"))
      (libsource (lib "easyedapro") (part "DB301V-3.5-2P-GN"))
    )
    (comp (ref "U19")
      (value "DRV8825PWPR")
      (footprint "easyedapro:HTSSOP-28_L9.7-W4.4-P0.65-LS6.4-BL-EP")
      (fields (field (name "Manufacturer") "TI(德州仪器)"))
      (libsource (lib "easyedapro") (part "DRV8825PWPR"))
    )
    (comp (ref "U20")
      (value "DRV8825PWPR")
      (footprint "easyedapro:HTSSOP-28_L9.7-W4.4-P0.65-LS6.4-BL-EP")
      (fields (field (name "Manufacturer") "TI(德州仪器)"))
      (libsource (lib "easyedapro") (part "DRV8825PWPR"))
    )
    (comp (ref "U21")
      (value "DB301V-3.5-2P-GN-S")
      (footprint "easyedapro:CONN-TH_DB301V-3.5-2P-GN")
      (fields (field (name "Manufacturer") "DORABO(地博电气)"))
      (libsource (lib "easyedapro") (part "DB301V-3.5-2P-GN"))
    )
    (comp (ref "U22")
      (value "DB301V-3.5-2P-GN-S")
      (footprint "easyedapro:CONN-TH_DB301V-3.5-2P-GN")
      (fields (field (name "Manufacturer") "DORABO(地博电气)"))
      (libsource (lib "easyedapro") (part "DB301V-3.5-2P-GN"))
    )
    (comp (ref "U23")
      (value "DB301V-3.5-2P-GN-S")
      (footprint "easyedapro:CONN-TH_DB301V-3.5-2P-GN")
      (fields (field (name "Manufacturer") "DORABO(地博电气)"))
      (libsource (lib "easyedapro") (part "DB301V-3.5-2P-GN"))
    )
    (comp (ref "U24")
      (value "DB301V-3.5-2P-GN-S")
      (footprint "easyedapro:CONN-TH_DB301V-3.5-2P-GN")
      (fields (field (name "Manufacturer") "DORABO(地博电气)"))
      (libsource (lib "easyedapro") (part "DB301V-3.5-2P-GN"))
    )
    (comp (ref "U25")
      (value "KF635-6.35-2P")
      (footprint "easyedapro:CONN-TH_P6.35_KF635-6.35-2P")
      (fields (field (name "Manufacturer") "KEFA(科发)"))
      (libsource (lib "easyedapro") (part "KF635-6.35-2P"))
    )
    (comp (ref "U26")
      (value "KF635-6.35-2P")
      (footprint "easyedapro:CONN-TH_P6.35_KF635-6.35-2P")
      (fields (field (name "Manufacturer") "KEFA(科发)"))
      (libsource (lib "easyedapro") (part "KF635-6.35-2P"))
    )
    (comp (ref "U27")
      (value "MBR20100DT")
      (footprint "easyedapro:TO-252-2_L6.5-W6.1-P4.58-LS10.0-BL")
      (fields (field (name "Manufacturer") "JUXING(钜兴)"))
      (libsource (lib "easyedapro") (part "MBR20100DT_C3011043"))
    )
    (comp (ref "U28")
      (value "KF635-6.35-2P")
      (footprint "easyedapro:CONN-TH_P6.35_KF635-6.35-2P")
      (fields (field (name "Manufacturer") "KEFA(科发)"))
      (libsource (lib "easyedapro") (part "KF635-6.35-2P"))
    )
    (comp (ref "U29")
      (value "KF635-6.35-2P")
      (footprint "easyedapro:CONN-TH_P6.35_KF635-6.35-2P")
      (fields (field (name "Manufacturer") "KEFA(科发)"))
      (libsource (lib "easyedapro") (part "KF635-6.35-2P"))
    )
    (comp (ref "U30")
      (value "MBR20100DT")
      (footprint "easyedapro:TO-252-2_L6.5-W6.1-P4.58-LS10.0-BL")
      (fields (field (name "Manufacturer") "JUXING(钜兴)"))
      (libsource (lib "easyedapro") (part "MBR20100DT_C3011043"))
    )
    (comp (ref "U31")
      (value "KF635-6.35-2P")
      (footprint "easyedapro:CONN-TH_P6.35_KF635-6.35-2P")
      (fields (field (name "Manufacturer") "KEFA(科发)"))
      (libsource (lib "easyedapro") (part "KF635-6.35-2P"))
    )
    (comp (ref "U32")
      (value "KF635-6.35-2P")
      (footprint "easyedapro:CONN-TH_P6.35_KF635-6.35-2P")
      (fields (field (name "Manufacturer") "KEFA(科发)"))
      (libsource (lib "easyedapro") (part "KF635-6.35-2P"))
    )
    (comp (ref "U33")
      (value "MBR20100DT")
      (footprint "easyedapro:TO-252-2_L6.5-W6.1-P4.58-LS10.0-BL")
      (fields (field (name "Manufacturer") "JUXING(钜兴)"))
      (libsource (lib "easyedapro") (part "MBR20100DT_C3011043"))
    )
    (comp (ref "U34")
      (value "DB301V-3.5-2P-GN-S")
      (footprint "easyedapro:CONN-TH_DB301V-3.5-2P-GN")
      (fields (field (name "Manufacturer") "DORABO(地博电气)"))
      (libsource (lib "easyedapro") (part "DB301V-3.5-2P-GN"))
    )
  )
  (nets
    (net (code "1") (name "/12V") (class "Default")
      (node (ref "C14") (pin "2") (pinfunction "2_2") (pintype "unspecified"))
      (node (ref "R14") (pin "2") (pinfunction "2_2") (pintype "input"))
      (node (ref "R32") (pin "2") (pinfunction "2_2") (pintype "input"))
      (node (ref "R35") (pin "2") (pinfunction "2_2") (pintype "input"))
      (node (ref "R38") (pin "2") (pinfunction "2_2") (pintype "input"))
      (node (ref "U11") (pin "2") (pinfunction "VOUT_2") (pintype "unspecified"))
    )
    (net (code "2") (name "/CH_EN") (class "Default")
      (node (ref "C5") (pin "2") (pinfunction "2_2") (pintype "unspecified"))
      (node (ref "R4") (pin "1") (pinfunction "1_1") (pintype "input"))
      (node (ref "SW2") (pin "4") (pinfunction "4_4") (pintype "input"))
      (node (ref "U2") (pin "3") (pinfunction "EN_3") (pintype "unspecified"))
    )
    (net (code "3") (name "/D+") (class "Default")
      (node (ref "D1") (pin "2") (pinfunction "2_2") (pintype "unspecified"))
      (node (ref "TP5") (pin "1") (pinfunction "1_1") (pintype "unspecified"))
      (node (ref "U2") (pin "14") (pinfunction "IO20_14") (pintype "unspecified"))
      (node (ref "U3") (pin "A6") (pinfunction "DP1_A6") (pintype "unspecified"))
      (node (ref "U3") (pin "B6") (pinfunction "DP2_B6") (pintype "unspecified"))
    )
    (net (code "4") (name "/D-") (class "Default")
      (node (ref "D2") (pin "2") (pinfunction "2_2") (pintype "unspecified"))
      (node (ref "TP4") (pin "1") (pinfunction "1_1") (pintype "unspecified"))
      (node (ref "U2") (pin "13") (pinfunction "IO19_13") (pintype "unspecified"))
      (node (ref "U3") (pin "A7") (pinfunction "DN1_A7") (pintype "unspecified"))
      (node (ref "U3") (pin "B7") (pinfunction "DN2_B7") (pintype "unspecified"))
    )
    (net (code "5") (name "/DIR1") (class "Default")
      (node (ref "TP8") (pin "1") (pinfunction "1_1") (pintype "unspecified"))
      (node (ref "U19") (pin "20") (pinfunction "DIR_20") (pintype "unspecified"))
      (node (ref "U2") (pin "6") (pinfunction "IO6_6") (pintype "unspecified"))
    )
    (net (code "6") (name "/DIR2") (class "Default")
      (node (ref "TP11") (pin "1") (pinfunction "1_1") (pintype "unspecified"))
      (node (ref "U2") (pin "9") (pinfunction "IO16_9") (pintype "unspecified"))
      (node (ref "U20") (pin "20") (pinfunction "DIR_20") (pintype "unspecified"))
    )
    (net (code "7") (name "/DIR3") (class "Default")
      (node (ref "TP14") (pin "1") (pinfunction "1_1") (pintype "unspecified"))
      (node (ref "U1") (pin "20") (pinfunction "DIR_20") (pintype "unspecified"))
      (node (ref "U2") (pin "12") (pinfunction "IO8_12") (pintype "unspecified"))
    )
    (net (code "8") (name "/DIR4") (class "Default")
      (node (ref "TP17") (pin "1") (pinfunction "1_1") (pintype "unspecified"))
      (node (ref "U15") (pin "20") (pinfunction "DIR_20") (pintype "unspecified"))
      (node (ref "U2") (pin "20") (pinfunction "IO12_20") (pintype "unspecified"))
    )
    (net (code "9") (name "/E_STOP") (class "Default")
      (node (ref "C24") (pin "1") (pinfunction "1_1") (pintype "unspecified"))
      (node (ref "R17") (pin "1") (pinfunction "1_1") (pintype "input"))
      (node (ref "U14") (pin "1") (pinfunction "1_1") (pintype "unspecified"))
      (node (ref "U2") (pin "39") (pinfunction "IO1_39") (pintype "unspecified"))
    )
    (net (code "10") (name "/GPIO0") (class "Default")
      (node (ref "C60") (pin "2") (pinfunction "2_2") (pintype "unspecified"))
      (node (ref "R3") (pin "1") (pinfunction "1_1") (pintype "input"))
      (node (ref "SW1") (pin "3") (pinfunction "3_3") (pintype "input"))
      (node (ref "SW1") (pin "4") (pinfunction "4_4") (pintype "input"))
      (node (ref "U2") (pin "27") (pinfunction "IO0_27") (pintype "unspecified"))
    )
    (net (code "11") (name "/LEDS") (class "Default")
      (node (ref "LED1") (pin "3") (pinfunction "DI_3") (pintype "unspecified"))
      (node (ref "U2") (pin "31") (pinfunction "IO38_31") (pintype "unspecified"))
    )
    (net (code "12") (name "/LIM_1") (class "Default")
      (node (ref "C25") (pin "1") (pinfunction "1_1") (pintype "unspecified"))
      (node (ref "R20") (pin "1") (pinfunction "1_1") (pintype "input"))
      (node (ref "U16") (pin "1") (pinfunction "1_1") (pintype "unspecified"))
      (node (ref "U2") (pin "38") (pinfunction "IO2_38") (pintype "unspecified"))
    )
    (net (code "13") (name "/LIM_2") (class "Default")
      (node (ref "H6") (pin "3") (pinfunction "3_3") (pintype "input"))
      (node (ref "R21") (pin "1") (pinfunction "1_1") (pintype "input"))
      (node (ref "U17") (pin "1") (pinfunction "1_1") (pintype "unspecified"))
      (node (ref "U2") (pin "37") (pinfunction "TXD0_37") (pintype "unspecified"))
    )
    (net (code "14") (name "/LIM_3") (class "Default")
      (node (ref "H6") (pin "2") (pinfunction "2_2") (pintype "input"))
      (node (ref "R22") (pin "1") (pinfunction "1_1") (pintype "input"))
      (node (ref "U18") (pin "1") (pinfunction "1_1") (pintype "unspecified"))
      (node (ref "U2") (pin "36") (pinfunction "RXD0_36") (pintype "unspecified"))
    )
    (net (code "15") (name "/LIM_4") (class "Default")
      (node (ref "C46") (pin "1") (pinfunction "1_1") (pintype "unspecified"))
      (node (ref "R27") (pin "1") (pinfunction "1_1") (pintype "input"))
      (node (ref "U2") (pin "35") (pinfunction "IO42_35") (pintype "unspecified"))
      (node (ref "U21") (pin "1") (pinfunction "1_1") (pintype "unspecified"))
    )
    (net (code "16") (name "/LIM_5") (class "Default")
      (node (ref "C47") (pin "1") (pinfunction "1_1") (pintype "unspecified"))
      (node (ref "R28") (pin "1") (pinfunction "1_1") (pintype "input"))
      (node (ref "U2") (pin "34") (pinfunction "IO41_34") (pintype "unspecified"))
      (node (ref "U22") (pin "1") (pinfunction "1_1") (pintype "unspecified"))
    )
    (net (code "17") (name "/LIM_6") (class "Default")
      (node (ref "C48") (pin "1") (pinfunction "1_1") (pintype "unspecified"))
      (node (ref "R29") (pin "1") (pinfunction "1_1") (pintype "input"))
      (node (ref "U2") (pin "33") (pinfunction "IO40_33") (pintype "unspecified"))
      (node (ref "U23") (pin "1") (pinfunction "1_1") (pintype "unspecified"))
    )
    (net (code "18") (name "/LIM_7") (class "Default")
      (node (ref "C49") (pin "1") (pinfunction "1_1") (pintype "unspecified"))
      (node (ref "R30") (pin "1") (pinfunction "1_1") (pintype "input"))
      (node (ref "U2") (pin "32") (pinfunction "IO39_32") (pintype "unspecified"))
      (node (ref "U24") (pin "1") (pinfunction "1_1") (pintype "unspecified"))
    )
    (net (code "19") (name "/MOSFET1") (class "Default")
      (node (ref "H3") (pin "1") (pinfunction "1_1") (pintype "unspecified"))
      (node (ref "Q8") (pin "1") (pinfunction "G_1") (pintype "unspecified"))
      (node (ref "R36") (pin "1") (pinfunction "1_1") (pintype "input"))
      (node (ref "U2") (pin "21") (pinfunction "IO13_21") (pintype "unspecified"))
    )
    (net (code "20") (name "/MOSFET2") (class "Default")
      (node (ref "H4") (pin "1") (pinfunction "1_1") (pintype "unspecified"))
      (node (ref "Q10") (pin "1") (pinfunction "G_1") (pintype "unspecified"))
      (node (ref "R39") (pin "1") (pinfunction "1_1") (pintype "input"))
      (node (ref "U2") (pin "22") (pinfunction "IO14_22") (pintype "unspecified"))
    )
    (net (code "21") (name "/MOSFET3") (class "Default")
      (node (ref "H1") (pin "1") (pinfunction "1_1") (pintype "unspecified"))
      (node (ref "Q4") (pin "1") (pinfunction "G_1") (pintype "unspecified"))
      (node (ref "R15") (pin "1") (pinfunction "1_1") (pintype "input"))
      (node (ref "U2") (pin "23") (pinfunction "IO21_23") (pintype "unspecified"))
    )
    (net (code "22") (name "/MOSFET4") (class "Default")
      (node (ref "H2") (pin "1") (pinfunction "1_1") (pintype "unspecified"))
      (node (ref "Q6") (pin "1") (pinfunction "G_1") (pintype "unspecified"))
      (node (ref "R33") (pin "1") (pinfunction "1_1") (pintype "input"))
      (node (ref "U2") (pin "24") (pinfunction "IO47_24") (pintype "unspecified"))
    )
    (net (code "23") (name "/NENBL1") (class "Default")
      (node (ref "TP7") (pin "1") (pinfunction "1_1") (pintype "unspecified"))
      (node (ref "U19") (pin "21") (pinfunction "NENBL_21") (pintype "unspecified"))
      (node (ref "U2") (pin "5") (pinfunction "IO5_5") (pintype "unspecified"))
    )
    (net (code "24") (name "/NENBL2") (class "Default")
      (node (ref "TP10") (pin "1") (pinfunction "1_1") (pintype "unspecified"))
      (node (ref "U2") (pin "8") (pinfunction "IO15_8") (pintype "unspecified"))
      (node (ref "U20") (pin "21") (pinfunction "NENBL_21") (pintype "unspecified"))
    )
    (net (code "25") (name "/NENBL3") (class "Default")
      (node (ref "TP13") (pin "1") (pinfunction "1_1") (pintype "unspecified"))
      (node (ref "U1") (pin "21") (pinfunction "NENBL_21") (pintype "unspecified"))
      (node (ref "U2") (pin "11") (pinfunction "IO18_11") (pintype "unspecified"))
    )
    (net (code "26") (name "/NENBL4") (class "Default")
      (node (ref "TP16") (pin "1") (pinfunction "1_1") (pintype "unspecified"))
      (node (ref "U15") (pin "21") (pinfunction "NENBL_21") (pintype "unspecified"))
      (node (ref "U2") (pin "19") (pinfunction "IO11_19") (pintype "unspecified"))
    )
    (net (code "27") (name "/NFAULT") (class "Default")
      (node (ref "C19") (pin "2") (pinfunction "2_2") (pintype "unspecified"))
      (node (ref "R16") (pin "1") (pinfunction "1_1") (pintype "input"))
      (node (ref "U1") (pin "18") (pinfunction "nFAULT_18") (pintype "unspecified"))
      (node (ref "U15") (pin "18") (pinfunction "nFAULT_18") (pintype "unspecified"))
      (node (ref "U19") (pin "18") (pinfunction "nFAULT_18") (pintype "unspecified"))
      (node (ref "U2") (pin "17") (pinfunction "IO9_17") (pintype "unspecified"))
      (node (ref "U20") (pin "18") (pinfunction "nFAULT_18") (pintype "unspecified"))
    )
    (net (code "28") (name "/STEP1") (class "Default")
      (node (ref "TP6") (pin "1") (pinfunction "1_1") (pintype "unspecified"))
      (node (ref "U19") (pin "22") (pinfunction "STEP_22") (pintype "unspecified"))
      (node (ref "U2") (pin "4") (pinfunction "IO4_4") (pintype "unspecified"))
    )
    (net (code "29") (name "/STEP2") (class "Default")
      (node (ref "TP9") (pin "1") (pinfunction "1_1") (pintype "unspecified"))
      (node (ref "U2") (pin "7") (pinfunction "IO7_7") (pintype "unspecified"))
      (node (ref "U20") (pin "22") (pinfunction "STEP_22") (pintype "unspecified"))
    )
    (net (code "30") (name "/STEP3") (class "Default")
      (node (ref "TP12") (pin "1") (pinfunction "1_1") (pintype "unspecified"))
      (node (ref "U1") (pin "22") (pinfunction "STEP_22") (pintype "unspecified"))
      (node (ref "U2") (pin "10") (pinfunction "IO17_10") (pintype "unspecified"))
    )
    (net (code "31") (name "/STEP4") (class "Default")
      (node (ref "TP15") (pin "1") (pinfunction "1_1") (pintype "unspecified"))
      (node (ref "U15") (pin "22") (pinfunction "STEP_22") (pintype "unspecified"))
      (node (ref "U2") (pin "18") (pinfunction "IO10_18") (pintype "unspecified"))
    )
    (net (code "32") (name "/VBUS") (class "Default")
      (node (ref "C61") (pin "1") (pinfunction "1_1") (pintype "input"))
      (node (ref "C62") (pin "1") (pinfunction "1_1") (pintype "input"))
      (node (ref "C63") (pin "1") (pinfunction "1_1") (pintype "input"))
      (node (ref "C64") (pin "1") (pinfunction "1_1") (pintype "input"))
      (node (ref "D3") (pin "2") (pinfunction "2_2") (pintype "unspecified"))
      (node (ref "D4") (pin "2") (pinfunction "A_2") (pintype "unspecified"))
      (node (ref "LED1") (pin "4") (pinfunction "VDD_4") (pintype "unspecified"))
      (node (ref "LED3") (pin "4") (pinfunction "VDD_4") (pintype "unspecified"))
      (node (ref "LED4") (pin "4") (pinfunction "VDD_4") (pintype "unspecified"))
      (node (ref "LED5") (pin "4") (pinfunction "VDD_4") (pintype "unspecified"))
      (node (ref "TP2") (pin "1") (pinfunction "1_1") (pintype "unspecified"))
      (node (ref "U3") (pin "A4B9") (pinfunction "VBUS_A4B9") (pintype "unspecified"))
      (node (ref "U3") (pin "A9B4") (pinfunction "VBUS_A9B4") (pintype "unspecified"))
      (node (ref "U34") (pin "2") (pinfunction "2_2") (pintype "unspecified"))
    )
    (net (code "33") (name "/VSYS") (class "Default")
      (node (ref "C2") (pin "1") (pinfunction "1_1") (pintype "unspecified"))
      (node (ref "C3") (pin "2") (pinfunction "2_2") (pintype "input"))
      (node (ref "D4") (pin "1") (pinfunction "K_1") (pintype "unspecified"))
      (node (ref "U6") (pin "2") (pinfunction "2_2") (pintype "unspecified"))
    )
    (net (code "34") (name "/V_MOSFET1") (class "Default")
      (node (ref "C52") (pin "1") (pinfunction "1_1") (pintype "unspecified"))
      (node (ref "C53") (pin "2") (pinfunction "2_2") (pintype "input"))
      (node (ref "U28") (pin "2") (pinfunction "2_2") (pintype "input"))
      (node (ref "U29") (pin "1") (pinfunction "1_1") (pintype "input"))
      (node (ref "U30") (pin "2") (pinfunction "K_2") (pintype "unspecified"))
    )
    (net (code "35") (name "/V_MOSFET2") (class "Default")
      (node (ref "C54") (pin "1") (pinfunction "1_1") (pintype "unspecified"))
      (node (ref "C55") (pin "2") (pinfunction "2_2") (pintype "input"))
      (node (ref "U31") (pin "2") (pinfunction "2_2") (pintype "input"))
      (node (ref "U32") (pin "1") (pinfunction "1_1") (pintype "input"))
      (node (ref "U33") (pin "2") (pinfunction "K_2") (pintype "unspecified"))
    )
    (net (code "36") (name "/V_MOSFET3") (class "Default")
      (node (ref "C10") (pin "1") (pinfunction "1_1") (pintype "unspecified"))
      (node (ref "C11") (pin "2") (pinfunction "2_2") (pintype "input"))
      (node (ref "U10") (pin "1") (pinfunction "1_1") (pintype "input"))
      (node (ref "U7") (pin "2") (pinfunction "K_2") (pintype "unspecified"))
      (node (ref "U9") (pin "2") (pinfunction "2_2") (pintype "input"))
    )
    (net (code "37") (name "/V_MOSFET4") (class "Default")
      (node (ref "C50") (pin "1") (pinfunction "1_1") (pintype "unspecified"))
      (node (ref "C51") (pin "2") (pinfunction "2_2") (pintype "input"))
      (node (ref "U25") (pin "2") (pinfunction "2_2") (pintype "input"))
      (node (ref "U26") (pin "1") (pinfunction "1_1") (pintype "input"))
      (node (ref "U27") (pin "2") (pinfunction "K_2") (pintype "unspecified"))
    )
    (net (code "38") (name "/V_STEPPER") (class "Default")
      (node (ref "C12") (pin "2") (pinfunction "2_2") (pintype "unspecified"))
      (node (ref "C18") (pin "2") (pinfunction "2_2") (pintype "input"))
      (node (ref "C23") (pin "1") (pinfunction "1_1") (pintype "unspecified"))
      (node (ref "C31") (pin "2") (pinfunction "2_2") (pintype "input"))
      (node (ref "C34") (pin "2") (pinfunction "2_2") (pintype "input"))
      (node (ref "C37") (pin "2") (pinfunction "2_2") (pintype "input"))
      (node (ref "C42") (pin "1") (pinfunction "1_1") (pintype "unspecified"))
      (node (ref "C45") (pin "1") (pinfunction "1_1") (pintype "unspecified"))
      (node (ref "C8") (pin "1") (pinfunction "1_1") (pintype "unspecified"))
      (node (ref "U1") (pin "11") (pinfunction "VMB_11") (pintype "unspecified"))
      (node (ref "U1") (pin "4") (pinfunction "VMA_4") (pintype "unspecified"))
      (node (ref "U11") (pin "3") (pinfunction "VIN_3") (pintype "unspecified"))
      (node (ref "U13") (pin "2") (pinfunction "2_2") (pintype "input"))
      (node (ref "U15") (pin "11") (pinfunction "VMB_11") (pintype "unspecified"))
      (node (ref "U15") (pin "4") (pinfunction "VMA_4") (pintype "unspecified"))
      (node (ref "U19") (pin "11") (pinfunction "VMB_11") (pintype "unspecified"))
      (node (ref "U19") (pin "4") (pinfunction "VMA_4") (pintype "unspecified"))
      (node (ref "U20") (pin "11") (pinfunction "VMB_11") (pintype "unspecified"))
      (node (ref "U20") (pin "4") (pinfunction "VMA_4") (pintype "unspecified"))
    )
    (net (code "39") (name "3V3") (class "Default")
      (node (ref "C1") (pin "2") (pinfunction "2_2") (pintype "unspecified"))
      (node (ref "C4") (pin "2") (pinfunction "2_2") (pintype "input"))
      (node (ref "R10") (pin "2") (pinfunction "2_2") (pintype "input"))
      (node (ref "R15") (pin "2") (pinfunction "2_2") (pintype "input"))
      (node (ref "R16") (pin "2") (pinfunction "2_2") (pintype "input"))
      (node (ref "R17") (pin "2") (pinfunction "2_2") (pintype "input"))
      (node (ref "R20") (pin "2") (pinfunction "2_2") (pintype "input"))
      (node (ref "R21") (pin "2") (pinfunction "2_2") (pintype "input"))
      (node (ref "R22") (pin "2") (pinfunction "2_2") (pintype "input"))
      (node (ref "R27") (pin "2") (pinfunction "2_2") (pintype "input"))
      (node (ref "R28") (pin "2") (pinfunction "2_2") (pintype "input"))
      (node (ref "R29") (pin "2") (pinfunction "2_2") (pintype "input"))
      (node (ref "R3") (pin "2") (pinfunction "2_2") (pintype "input"))
      (node (ref "R30") (pin "2") (pinfunction "2_2") (pintype "input"))
      (node (ref "R33") (pin "2") (pinfunction "2_2") (pintype "input"))
      (node (ref "R36") (pin "2") (pinfunction "2_2") (pintype "input"))
      (node (ref "R39") (pin "2") (pinfunction "2_2") (pintype "input"))
      (node (ref "R4") (pin "2") (pinfunction "2_2") (pintype "input"))
      (node (ref "U2") (pin "2") (pinfunction "3V3_2") (pintype "unspecified"))
      (node (ref "U4") (pin "2") (pinfunction "VOUT(TAB)_2") (pintype "unspecified"))
      (node (ref "U5") (pin "1") (pinfunction "1_1") (pintype "unspecified"))
    )
    (net (code "40") (name "GND") (class "Default")
      (node (ref "C1") (pin "1") (pinfunction "1_1") (pintype "unspecified"))
      (node (ref "C10") (pin "2") (pinfunction "2_2") (pintype "unspecified"))
      (node (ref "C11") (pin "1") (pinfunction "1_1") (pintype "input"))
      (node (ref "C12") (pin "1") (pinfunction "1_1") (pintype "unspecified"))
      (node (ref "C14") (pin "1") (pinfunction "1_1") (pintype "unspecified"))
      (node (ref "C15") (pin "1") (pinfunction "1_1") (pintype "input"))
      (node (ref "C18") (pin "1") (pinfunction "1_1") (pintype "input"))
      (node (ref "C19") (pin "1") (pinfunction "1_1") (pintype "unspecified"))
      (node (ref "C2") (pin "2") (pinfunction "2_2") (pintype "unspecified"))
      (node (ref "C22") (pin "1") (pinfunction "1_1") (pintype "input"))
      (node (ref "C24") (pin "2") (pinfunction "2_2") (pintype "unspecified"))
      (node (ref "C25") (pin "2") (pinfunction "2_2") (pintype "unspecified"))
      (node (ref "C3") (pin "1") (pinfunction "1_1") (pintype "input"))
      (node (ref "C31") (pin "1") (pinfunction "1_1") (pintype "input"))
      (node (ref "C34") (pin "1") (pinfunction "1_1") (pintype "input"))
      (node (ref "C37") (pin "1") (pinfunction "1_1") (pintype "input"))
      (node (ref "C4") (pin "1") (pinfunction "1_1") (pintype "input"))
      (node (ref "C41") (pin "1") (pinfunction "1_1") (pintype "input"))
      (node (ref "C44") (pin "1") (pinfunction "1_1") (pintype "input"))
      (node (ref "C46") (pin "2") (pinfunction "2_2") (pintype "unspecified"))
      (node (ref "C47") (pin "2") (pinfunction "2_2") (pintype "unspecified"))
      (node (ref "C48") (pin "2") (pinfunction "2_2") (pintype "unspecified"))
      (node (ref "C49") (pin "2") (pinfunction "2_2") (pintype "unspecified"))
      (node (ref "C5") (pin "1") (pinfunction "1_1") (pintype "unspecified"))
      (node (ref "C50") (pin "2") (pinfunction "2_2") (pintype "unspecified"))
      (node (ref "C51") (pin "1") (pinfunction "1_1") (pintype "input"))
      (node (ref "C52") (pin "2") (pinfunction "2_2") (pintype "unspecified"))
      (node (ref "C53") (pin "1") (pinfunction "1_1") (pintype "input"))
      (node (ref "C54") (pin "2") (pinfunction "2_2") (pintype "unspecified"))
      (node (ref "C55") (pin "1") (pinfunction "1_1") (pintype "input"))
      (node (ref "C60") (pin "1") (pinfunction "1_1") (pintype "unspecified"))
      (node (ref "C61") (pin "2") (pinfunction "2_2") (pintype "input"))
      (node (ref "C62") (pin "2") (pinfunction "2_2") (pintype "input"))
      (node (ref "C63") (pin "2") (pinfunction "2_2") (pintype "input"))
      (node (ref "C64") (pin "2") (pinfunction "2_2") (pintype "input"))
      (node (ref "D1") (pin "1") (pinfunction "1_1") (pintype "unspecified"))
      (node (ref "D2") (pin "1") (pinfunction "1_1") (pintype "unspecified"))
      (node (ref "D3") (pin "1") (pinfunction "1_1") (pintype "unspecified"))
      (node (ref "D6") (pin "1") (pinfunction "1_1") (pintype "unspecified"))
      (node (ref "D7") (pin "1") (pinfunction "1_1") (pintype "unspecified"))
      (node (ref "D8") (pin "1") (pinfunction "1_1") (pintype "unspecified"))
      (node (ref "D9") (pin "1") (pinfunction "1_1") (pintype "unspecified"))
      (node (ref "H1") (pin "2") (pinfunction "2_2") (pintype "unspecified"))
      (node (ref "H2") (pin "2") (pinfunction "2_2") (pintype "unspecified"))
      (node (ref "H3") (pin "2") (pinfunction "2_2") (pintype "unspecified"))
      (node (ref "H4") (pin "2") (pinfunction "2_2") (pintype "unspecified"))
      (node (ref "H5") (pin "2") (pinfunction "2_2") (pintype "unspecified"))
      (node (ref "H6") (pin "1") (pinfunction "1_1") (pintype "input"))
      (node (ref "LED1") (pin "2") (pinfunction "GND_2") (pintype "unspecified"))
      (node (ref "LED2") (pin "1") (pinfunction "K_1") (pintype "unspecified"))
      (node (ref "LED3") (pin "2") (pinfunction "GND_2") (pintype "unspecified"))
      (node (ref "LED4") (pin "2") (pinfunction "GND_2") (pintype "unspecified"))
      (node (ref "LED5") (pin "2") (pinfunction "GND_2") (pintype "unspecified"))
      (node (ref "Q10") (pin "2") (pinfunction "S_2") (pintype "unspecified"))
      (node (ref "Q3") (pin "3") (pinfunction "S_3") (pintype "unspecified"))
      (node (ref "Q4") (pin "2") (pinfunction "S_2") (pintype "unspecified"))
      (node (ref "Q5") (pin "3") (pinfunction "S_3") (pintype "unspecified"))
      (node (ref "Q6") (pin "2") (pinfunction "S_2") (pintype "unspecified"))
      (node (ref "Q7") (pin "3") (pinfunction "S_3") (pintype "unspecified"))
      (node (ref "Q8") (pin "2") (pinfunction "S_2") (pintype "unspecified"))
      (node (ref "Q9") (pin "3") (pinfunction "S_3") (pintype "unspecified"))
      (node (ref "R1") (pin "2") (pinfunction "2_2") (pintype "input"))
      (node (ref "R11") (pin "2") (pinfunction "2_2") (pintype "unspecified"))
      (node (ref "R12") (pin "2") (pinfunction "2_2") (pintype "unspecified"))
      (node (ref "R18") (pin "2") (pinfunction "2_2") (pintype "unspecified"))
      (node (ref "R19") (pin "2") (pinfunction "2_2") (pintype "unspecified"))
      (node (ref "R2") (pin "2") (pinfunction "2_2") (pintype "input"))
      (node (ref "R23") (pin "2") (pinfunction "2_2") (pintype "unspecified"))
      (node (ref "R24") (pin "2") (pinfunction "2_2") (pintype "unspecified"))
      (node (ref "R25") (pin "2") (pinfunction "2_2") (pintype "unspecified"))
      (node (ref "R26") (pin "2") (pinfunction "2_2") (pintype "unspecified"))
      (node (ref "RJ1") (pin "1") (pinfunction "1_1") (pintype "unspecified"))
      (node (ref "RJ2") (pin "1") (pinfunction "1_1") (pintype "unspecified"))
      (node (ref "RJ3") (pin "1") (pinfunction "1_1") (pintype "unspecified"))
      (node (ref "RJ4") (pin "1") (pinfunction "1_1") (pintype "unspecified"))
      (node (ref "SW1") (pin "1") (pinfunction "1_1") (pintype "input"))
      (node (ref "SW1") (pin "2") (pinfunction "2_2") (pintype "input"))
      (node (ref "SW2") (pin "1") (pinfunction "1_1") (pintype "input"))
      (node (ref "SW2") (pin "2") (pinfunction "2_2") (pintype "input"))
      (node (ref "TP18") (pin "1") (pinfunction "1_1") (pintype "unspecified"))
      (node (ref "U1") (pin "14") (pinfunction "GND_14") (pintype "unspecified"))
      (node (ref "U1") (pin "28") (pinfunction "GND_28") (pintype "unspecified"))
      (node (ref "U1") (pin "29") (pinfunction "EP_29") (pintype "unspecified"))
      (node (ref "U11") (pin "1") (pinfunction "GND_1") (pintype "unspecified"))
      (node (ref "U13") (pin "1") (pinfunction "1_1") (pintype "input"))
      (node (ref "U14") (pin "2") (pinfunction "2_2") (pintype "unspecified"))
      (node (ref "U15") (pin "14") (pinfunction "GND_14") (pintype "unspecified"))
      (node (ref "U15") (pin "28") (pinfunction "GND_28") (pintype "unspecified"))
      (node (ref "U15") (pin "29") (pinfunction "EP_29") (pintype "unspecified"))
      (node (ref "U16") (pin "2") (pinfunction "2_2") (pintype "unspecified"))
      (node (ref "U17") (pin "2") (pinfunction "2_2") (pintype "unspecified"))
      (node (ref "U18") (pin "2") (pinfunction "2_2") (pintype "unspecified"))
      (node (ref "U19") (pin "14") (pinfunction "GND_14") (pintype "unspecified"))
      (node (ref "U19") (pin "28") (pinfunction "GND_28") (pintype "unspecified"))
      (node (ref "U19") (pin "29") (pinfunction "EP_29") (pintype "unspecified"))
      (node (ref "U2") (pin "1") (pinfunction "GND_1") (pintype "unspecified"))
      (node (ref "U2") (pin "40") (pinfunction "GND_40") (pintype "unspecified"))
      (node (ref "U2") (pin "41") (pinfunction "GND_41") (pintype "unspecified"))
      (node (ref "U20") (pin "14") (pinfunction "GND_14") (pintype "unspecified"))
      (node (ref "U20") (pin "28") (pinfunction "GND_28") (pintype "unspecified"))
      (node (ref "U20") (pin "29") (pinfunction "EP_29") (pintype "unspecified"))
      (node (ref "U21") (pin "2") (pinfunction "2_2") (pintype "unspecified"))
      (node (ref "U22") (pin "2") (pinfunction "2_2") (pintype "unspecified"))
      (node (ref "U23") (pin "2") (pinfunction "2_2") (pintype "unspecified"))
      (node (ref "U24") (pin "2") (pinfunction "2_2") (pintype "unspecified"))
      (node (ref "U25") (pin "1") (pinfunction "1_1") (pintype "input"))
      (node (ref "U28") (pin "1") (pinfunction "1_1") (pintype "input"))
      (node (ref "U3") (pin "12") (pinfunction "12_12") (pintype "unspecified"))
      (node (ref "U3") (pin "13") (pinfunction "13_13") (pintype "unspecified"))
      (node (ref "U3") (pin "14") (pinfunction "14_14") (pintype "unspecified"))
      (node (ref "U3") (pin "15") (pinfunction "15_15") (pintype "unspecified"))
      (node (ref "U3") (pin "A12B1") (pinfunction "GND_A12B1") (pintype "unspecified"))
      (node (ref "U3") (pin "A1B12") (pinfunction "GND_A1B12") (pintype "unspecified"))
      (node (ref "U31") (pin "1") (pinfunction "1_1") (pintype "input"))
      (node (ref "U34") (pin "1") (pinfunction "1_1") (pintype "unspecified"))
      (node (ref "U4") (pin "1") (pinfunction "ADJ(GND)_1") (pintype "unspecified"))
      (node (ref "U5") (pin "2") (pinfunction "2_2") (pintype "unspecified"))
      (node (ref "U9") (pin "1") (pinfunction "1_1") (pintype "input"))
    )
    (net (code "41") (name "Net-(LED1-DO)") (class "Default")
      (node (ref "LED1") (pin "1") (pinfunction "DO_1") (pintype "unspecified"))
      (node (ref "LED3") (pin "3") (pinfunction "DI_3") (pintype "unspecified"))
    )
    (net (code "42") (name "Net-(LED2-A)") (class "Default")
      (node (ref "LED2") (pin "2") (pinfunction "A_2") (pintype "unspecified"))
      (node (ref "R10") (pin "1") (pinfunction "1_1") (pintype "input"))
    )
    (net (code "43") (name "Net-(LED3-DO)") (class "Default")
      (node (ref "LED3") (pin "1") (pinfunction "DO_1") (pintype "unspecified"))
      (node (ref "LED4") (pin "3") (pinfunction "DI_3") (pintype "unspecified"))
    )
    (net (code "44") (name "Net-(LED4-DO)") (class "Default")
      (node (ref "LED4") (pin "1") (pinfunction "DO_1") (pintype "unspecified"))
      (node (ref "LED5") (pin "3") (pinfunction "DI_3") (pintype "unspecified"))
    )
    (net (code "45") (name "Net-(LED5-DO)") (class "Default")
      (node (ref "LED5") (pin "1") (pinfunction "DO_1") (pintype "unspecified"))
      (node (ref "TP1") (pin "1") (pinfunction "1_1") (pintype "unspecified"))
    )
    (net (code "46") (name "Net-(Q3-D)") (class "Default")
      (node (ref "D6") (pin "2") (pinfunction "2_2") (pintype "unspecified"))
      (node (ref "Q3") (pin "4") (pinfunction "D_4") (pintype "unspecified"))
      (node (ref "U10") (pin "2") (pinfunction "2_2") (pintype "input"))
      (node (ref "U7") (pin "1") (pinfunction "A_1") (pintype "unspecified"))
      (node (ref "U7") (pin "3") (pinfunction "A_3") (pintype "unspecified"))
    )
    (net (code "47") (name "Net-(Q3-G)") (class "Default")
      (node (ref "Q3") (pin "1") (pinfunction "G_1") (pintype "unspecified"))
      (node (ref "R13") (pin "2") (pinfunction "2_2") (pintype "input"))
    )
    (net (code "48") (name "Net-(Q4-D)") (class "Default")
      (node (ref "Q4") (pin "3") (pinfunction "D_3") (pintype "unspecified"))
      (node (ref "R13") (pin "1") (pinfunction "1_1") (pintype "input"))
      (node (ref "R14") (pin "1") (pinfunction "1_1") (pintype "input"))
    )
    (net (code "49") (name "Net-(Q5-D)") (class "Default")
      (node (ref "D7") (pin "2") (pinfunction "2_2") (pintype "unspecified"))
      (node (ref "Q5") (pin "4") (pinfunction "D_4") (pintype "unspecified"))
      (node (ref "U26") (pin "2") (pinfunction "2_2") (pintype "input"))
      (node (ref "U27") (pin "1") (pinfunction "A_1") (pintype "unspecified"))
      (node (ref "U27") (pin "3") (pinfunction "A_3") (pintype "unspecified"))
    )
    (net (code "50") (name "Net-(Q5-G)") (class "Default")
      (node (ref "Q5") (pin "1") (pinfunction "G_1") (pintype "unspecified"))
      (node (ref "R31") (pin "2") (pinfunction "2_2") (pintype "input"))
    )
    (net (code "51") (name "Net-(Q6-D)") (class "Default")
      (node (ref "Q6") (pin "3") (pinfunction "D_3") (pintype "unspecified"))
      (node (ref "R31") (pin "1") (pinfunction "1_1") (pintype "input"))
      (node (ref "R32") (pin "1") (pinfunction "1_1") (pintype "input"))
    )
    (net (code "52") (name "Net-(Q7-D)") (class "Default")
      (node (ref "D8") (pin "2") (pinfunction "2_2") (pintype "unspecified"))
      (node (ref "Q7") (pin "4") (pinfunction "D_4") (pintype "unspecified"))
      (node (ref "U29") (pin "2") (pinfunction "2_2") (pintype "input"))
      (node (ref "U30") (pin "1") (pinfunction "A_1") (pintype "unspecified"))
      (node (ref "U30") (pin "3") (pinfunction "A_3") (pintype "unspecified"))
    )
    (net (code "53") (name "Net-(Q7-G)") (class "Default")
      (node (ref "Q7") (pin "1") (pinfunction "G_1") (pintype "unspecified"))
      (node (ref "R34") (pin "2") (pinfunction "2_2") (pintype "input"))
    )
    (net (code "54") (name "Net-(Q8-D)") (class "Default")
      (node (ref "Q8") (pin "3") (pinfunction "D_3") (pintype "unspecified"))
      (node (ref "R34") (pin "1") (pinfunction "1_1") (pintype "input"))
      (node (ref "R35") (pin "1") (pinfunction "1_1") (pintype "input"))
    )
    (net (code "55") (name "Net-(Q9-D)") (class "Default")
      (node (ref "D9") (pin "2") (pinfunction "2_2") (pintype "unspecified"))
      (node (ref "Q9") (pin "4") (pinfunction "D_4") (pintype "unspecified"))
      (node (ref "U32") (pin "2") (pinfunction "2_2") (pintype "input"))
      (node (ref "U33") (pin "1") (pinfunction "A_1") (pintype "unspecified"))
      (node (ref "U33") (pin "3") (pinfunction "A_3") (pintype "unspecified"))
    )
    (net (code "56") (name "Net-(Q9-G)") (class "Default")
      (node (ref "Q9") (pin "1") (pinfunction "G_1") (pintype "unspecified"))
      (node (ref "R37") (pin "2") (pinfunction "2_2") (pintype "input"))
    )
    (net (code "57") (name "Net-(Q10-D)") (class "Default")
      (node (ref "Q10") (pin "3") (pinfunction "D_3") (pintype "unspecified"))
      (node (ref "R37") (pin "1") (pinfunction "1_1") (pintype "input"))
      (node (ref "R38") (pin "1") (pinfunction "1_1") (pintype "input"))
    )
    (net (code "58") (name "Net-(U1-AOUT1)") (class "Default")
      (node (ref "P1") (pin "4") (pinfunction "4_4") (pintype "unspecified"))
      (node (ref "U1") (pin "5") (pinfunction "AOUT1_5") (pintype "unspecified"))
    )
    (net (code "59") (name "Net-(U1-AOUT2)") (class "Default")
      (node (ref "P1") (pin "3") (pinfunction "3_3") (pintype "unspecified"))
      (node (ref "U1") (pin "7") (pinfunction "AOUT2_7") (pintype "unspecified"))
    )
    (net (code "60") (name "Net-(U1-AVREF)") (class "Default")
      (node (ref "RJ1") (pin "2") (pinfunction "2_2") (pintype "unspecified"))
      (node (ref "U1") (pin "12") (pinfunction "AVREF_12") (pintype "unspecified"))
      (node (ref "U1") (pin "13") (pinfunction "BVREF_13") (pintype "unspecified"))
    )
    (net (code "61") (name "Net-(U1-BOUT1)") (class "Default")
      (node (ref "P1") (pin "1") (pinfunction "1_1") (pintype "unspecified"))
      (node (ref "U1") (pin "10") (pinfunction "BOUT1_10") (pintype "unspecified"))
    )
    (net (code "62") (name "Net-(U1-BOUT2)") (class "Default")
      (node (ref "P1") (pin "2") (pinfunction "2_2") (pintype "unspecified"))
      (node (ref "U1") (pin "8") (pinfunction "BOUT2_8") (pintype "unspecified"))
    )
    (net (code "63") (name "Net-(U1-CP1)") (class "Default")
      (node (ref "C9") (pin "2") (pinfunction "2_2") (pintype "input"))
      (node (ref "U1") (pin "1") (pinfunction "CP1_1") (pintype "unspecified"))
    )
    (net (code "64") (name "Net-(U1-CP2)") (class "Default")
      (node (ref "C9") (pin "1") (pinfunction "1_1") (pintype "input"))
      (node (ref "U1") (pin "2") (pinfunction "CP2_2") (pintype "unspecified"))
    )
    (net (code "65") (name "Net-(U1-ISENA)") (class "Default")
      (node (ref "R11") (pin "1") (pinfunction "1_1") (pintype "unspecified"))
      (node (ref "U1") (pin "6") (pinfunction "ISENA_6") (pintype "unspecified"))
    )
    (net (code "66") (name "Net-(U1-ISENB)") (class "Default")
      (node (ref "R12") (pin "1") (pinfunction "1_1") (pintype "unspecified"))
      (node (ref "U1") (pin "9") (pinfunction "ISENB_9") (pintype "unspecified"))
    )
    (net (code "67") (name "Net-(U1-MODE0)") (class "Default")
      (node (ref "SW3") (pin "6") (pinfunction "6_6") (pintype "unspecified"))
      (node (ref "U1") (pin "24") (pinfunction "MODE0_24") (pintype "unspecified"))
    )
    (net (code "68") (name "Net-(U1-MODE1)") (class "Default")
      (node (ref "SW3") (pin "5") (pinfunction "5_5") (pintype "unspecified"))
      (node (ref "U1") (pin "25") (pinfunction "MODE1_25") (pintype "unspecified"))
    )
    (net (code "69") (name "Net-(U1-MODE2)") (class "Default")
      (node (ref "SW3") (pin "4") (pinfunction "4_4") (pintype "unspecified"))
      (node (ref "U1") (pin "26") (pinfunction "MODE2_26") (pintype "unspecified"))
    )
    (net (code "70") (name "Net-(U1-V3P3OUT)") (class "Default")
      (node (ref "C15") (pin "2") (pinfunction "2_2") (pintype "input"))
      (node (ref "RJ1") (pin "3") (pinfunction "3_3") (pintype "unspecified"))
      (node (ref "SW3") (pin "1") (pinfunction "1_1") (pintype "unspecified"))
      (node (ref "SW3") (pin "2") (pinfunction "2_2") (pintype "unspecified"))
      (node (ref "SW3") (pin "3") (pinfunction "3_3") (pintype "unspecified"))
      (node (ref "U1") (pin "15") (pinfunction "V3P3OUT_15") (pintype "unspecified"))
      (node (ref "U1") (pin "16") (pinfunction "nRESET_16") (pintype "unspecified"))
      (node (ref "U1") (pin "17") (pinfunction "nSLEEP_17") (pintype "unspecified"))
    )
    (net (code "71") (name "Net-(U1-VCP)") (class "Default")
      (node (ref "C8") (pin "2") (pinfunction "2_2") (pintype "unspecified"))
      (node (ref "U1") (pin "3") (pinfunction "VCP_3") (pintype "unspecified"))
    )
    (net (code "72") (name "Net-(U2-IO48)") (class "Default")
      (node (ref "H5") (pin "1") (pinfunction "1_1") (pintype "unspecified"))
      (node (ref "U2") (pin "25") (pinfunction "IO48_25") (pintype "unspecified"))
    )
    (net (code "73") (name "Net-(U3-CC1)") (class "Default")
      (node (ref "R1") (pin "1") (pinfunction "1_1") (pintype "input"))
      (node (ref "U3") (pin "A5") (pinfunction "CC1_A5") (pintype "unspecified"))
    )
    (net (code "74") (name "Net-(U3-CC2)") (class "Default")
      (node (ref "R2") (pin "1") (pinfunction "1_1") (pintype "input"))
      (node (ref "U3") (pin "B5") (pinfunction "CC2_B5") (pintype "unspecified"))
    )
    (net (code "75") (name "Net-(U4-VIN)") (class "Default")
      (node (ref "U4") (pin "3") (pinfunction "VIN_3") (pintype "unspecified"))
      (node (ref "U6") (pin "1") (pinfunction "1_1") (pintype "unspecified"))
    )
    (net (code "76") (name "Net-(U15-AOUT1)") (class "Default")
      (node (ref "P2") (pin "4") (pinfunction "4_4") (pintype "unspecified"))
      (node (ref "U15") (pin "5") (pinfunction "AOUT1_5") (pintype "unspecified"))
    )
    (net (code "77") (name "Net-(U15-AOUT2)") (class "Default")
      (node (ref "P2") (pin "3") (pinfunction "3_3") (pintype "unspecified"))
      (node (ref "U15") (pin "7") (pinfunction "AOUT2_7") (pintype "unspecified"))
    )
    (net (code "78") (name "Net-(U15-AVREF)") (class "Default")
      (node (ref "RJ2") (pin "2") (pinfunction "2_2") (pintype "unspecified"))
      (node (ref "U15") (pin "12") (pinfunction "AVREF_12") (pintype "unspecified"))
      (node (ref "U15") (pin "13") (pinfunction "BVREF_13") (pintype "unspecified"))
    )
    (net (code "79") (name "Net-(U15-BOUT1)") (class "Default")
      (node (ref "P2") (pin "1") (pinfunction "1_1") (pintype "unspecified"))
      (node (ref "U15") (pin "10") (pinfunction "BOUT1_10") (pintype "unspecified"))
    )
    (net (code "80") (name "Net-(U15-BOUT2)") (class "Default")
      (node (ref "P2") (pin "2") (pinfunction "2_2") (pintype "unspecified"))
      (node (ref "U15") (pin "8") (pinfunction "BOUT2_8") (pintype "unspecified"))
    )
    (net (code "81") (name "Net-(U15-CP1)") (class "Default")
      (node (ref "C21") (pin "2") (pinfunction "2_2") (pintype "input"))
      (node (ref "U15") (pin "1") (pinfunction "CP1_1") (pintype "unspecified"))
    )
    (net (code "82") (name "Net-(U15-CP2)") (class "Default")
      (node (ref "C21") (pin "1") (pinfunction "1_1") (pintype "input"))
      (node (ref "U15") (pin "2") (pinfunction "CP2_2") (pintype "unspecified"))
    )
    (net (code "83") (name "Net-(U15-ISENA)") (class "Default")
      (node (ref "R18") (pin "1") (pinfunction "1_1") (pintype "unspecified"))
      (node (ref "U15") (pin "6") (pinfunction "ISENA_6") (pintype "unspecified"))
    )
    (net (code "84") (name "Net-(U15-ISENB)") (class "Default")
      (node (ref "R19") (pin "1") (pinfunction "1_1") (pintype "unspecified"))
      (node (ref "U15") (pin "9") (pinfunction "ISENB_9") (pintype "unspecified"))
    )
    (net (code "85") (name "Net-(U15-MODE0)") (class "Default")
      (node (ref "SW4") (pin "6") (pinfunction "6_6") (pintype "unspecified"))
      (node (ref "U15") (pin "24") (pinfunction "MODE0_24") (pintype "unspecified"))
    )
    (net (code "86") (name "Net-(U15-MODE1)") (class "Default")
      (node (ref "SW4") (pin "5") (pinfunction "5_5") (pintype "unspecified"))
      (node (ref "U15") (pin "25") (pinfunction "MODE1_25") (pintype "unspecified"))
    )
    (net (code "87") (name "Net-(U15-MODE2)") (class "Default")
      (node (ref "SW4") (pin "4") (pinfunction "4_4") (pintype "unspecified"))
      (node (ref "U15") (pin "26") (pinfunction "MODE2_26") (pintype "unspecified"))
    )
    (net (code "88") (name "Net-(U15-V3P3OUT)") (class "Default")
      (node (ref "C22") (pin "2") (pinfunction "2_2") (pintype "input"))
      (node (ref "RJ2") (pin "3") (pinfunction "3_3") (pintype "unspecified"))
      (node (ref "SW4") (pin "1") (pinfunction "1_1") (pintype "unspecified"))
      (node (ref "SW4") (pin "2") (pinfunction "2_2") (pintype "unspecified"))
      (node (ref "SW4") (pin "3") (pinfunction "3_3") (pintype "unspecified"))
      (node (ref "U15") (pin "15") (pinfunction "V3P3OUT_15") (pintype "unspecified"))
      (node (ref "U15") (pin "16") (pinfunction "nRESET_16") (pintype "unspecified"))
      (node (ref "U15") (pin "17") (pinfunction "nSLEEP_17") (pintype "unspecified"))
    )
    (net (code "89") (name "Net-(U15-VCP)") (class "Default")
      (node (ref "C23") (pin "2") (pinfunction "2_2") (pintype "unspecified"))
      (node (ref "U15") (pin "3") (pinfunction "VCP_3") (pintype "unspecified"))
    )
    (net (code "90") (name "Net-(U19-AOUT1)") (class "Default")
      (node (ref "P3") (pin "4") (pinfunction "4_4") (pintype "unspecified"))
      (node (ref "U19") (pin "5") (pinfunction "AOUT1_5") (pintype "unspecified"))
    )
    (net (code "91") (name "Net-(U19-AOUT2)") (class "Default")
      (node (ref "P3") (pin "3") (pinfunction "3_3") (pintype "unspecified"))
      (node (ref "U19") (pin "7") (pinfunction "AOUT2_7") (pintype "unspecified"))
    )
    (net (code "92") (name "Net-(U19-AVREF)") (class "Default")
      (node (ref "RJ3") (pin "2") (pinfunction "2_2") (pintype "unspecified"))
      (node (ref "U19") (pin "12") (pinfunction "AVREF_12") (pintype "unspecified"))
      (node (ref "U19") (pin "13") (pinfunction "BVREF_13") (pintype "unspecified"))
    )
    (net (code "93") (name "Net-(U19-BOUT1)") (class "Default")
      (node (ref "P3") (pin "1") (pinfunction "1_1") (pintype "unspecified"))
      (node (ref "U19") (pin "10") (pinfunction "BOUT1_10") (pintype "unspecified"))
    )
    (net (code "94") (name "Net-(U19-BOUT2)") (class "Default")
      (node (ref "P3") (pin "2") (pinfunction "2_2") (pintype "unspecified"))
      (node (ref "U19") (pin "8") (pinfunction "BOUT2_8") (pintype "unspecified"))
    )
    (net (code "95") (name "Net-(U19-CP1)") (class "Default")
      (node (ref "C40") (pin "2") (pinfunction "2_2") (pintype "input"))
      (node (ref "U19") (pin "1") (pinfunction "CP1_1") (pintype "unspecified"))
    )
    (net (code "96") (name "Net-(U19-CP2)") (class "Default")
      (node (ref "C40") (pin "1") (pinfunction "1_1") (pintype "input"))
      (node (ref "U19") (pin "2") (pinfunction "CP2_2") (pintype "unspecified"))
    )
    (net (code "97") (name "Net-(U19-ISENA)") (class "Default")
      (node (ref "R23") (pin "1") (pinfunction "1_1") (pintype "unspecified"))
      (node (ref "U19") (pin "6") (pinfunction "ISENA_6") (pintype "unspecified"))
    )
    (net (code "98") (name "Net-(U19-ISENB)") (class "Default")
      (node (ref "R24") (pin "1") (pinfunction "1_1") (pintype "unspecified"))
      (node (ref "U19") (pin "9") (pinfunction "ISENB_9") (pintype "unspecified"))
    )
    (net (code "99") (name "Net-(U19-MODE0)") (class "Default")
      (node (ref "SW5") (pin "6") (pinfunction "6_6") (pintype "unspecified"))
      (node (ref "U19") (pin "24") (pinfunction "MODE0_24") (pintype "unspecified"))
    )
    (net (code "100") (name "Net-(U19-MODE1)") (class "Default")
      (node (ref "SW5") (pin "5") (pinfunction "5_5") (pintype "unspecified"))
      (node (ref "U19") (pin "25") (pinfunction "MODE1_25") (pintype "unspecified"))
    )
    (net (code "101") (name "Net-(U19-MODE2)") (class "Default")
      (node (ref "SW5") (pin "4") (pinfunction "4_4") (pintype "unspecified"))
      (node (ref "U19") (pin "26") (pinfunction "MODE2_26") (pintype "unspecified"))
    )
    (net (code "102") (name "Net-(U19-V3P3OUT)") (class "Default")
      (node (ref "C41") (pin "2") (pinfunction "2_2") (pintype "input"))
      (node (ref "RJ3") (pin "3") (pinfunction "3_3") (pintype "unspecified"))
      (node (ref "SW5") (pin "1") (pinfunction "1_1") (pintype "unspecified"))
      (node (ref "SW5") (pin "2") (pinfunction "2_2") (pintype "unspecified"))
      (node (ref "SW5") (pin "3") (pinfunction "3_3") (pintype "unspecified"))
      (node (ref "U19") (pin "15") (pinfunction "V3P3OUT_15") (pintype "unspecified"))
      (node (ref "U19") (pin "16") (pinfunction "nRESET_16") (pintype "unspecified"))
      (node (ref "U19") (pin "17") (pinfunction "nSLEEP_17") (pintype "unspecified"))
    )
    (net (code "103") (name "Net-(U19-VCP)") (class "Default")
      (node (ref "C42") (pin "2") (pinfunction "2_2") (pintype "unspecified"))
      (node (ref "U19") (pin "3") (pinfunction "VCP_3") (pintype "unspecified"))
    )
    (net (code "104") (name "Net-(U20-AOUT1)") (class "Default")
      (node (ref "P4") (pin "4") (pinfunction "4_4") (pintype "unspecified"))
      (node (ref "U20") (pin "5") (pinfunction "AOUT1_5") (pintype "unspecified"))
    )
    (net (code "105") (name "Net-(U20-AOUT2)") (class "Default")
      (node (ref "P4") (pin "3") (pinfunction "3_3") (pintype "unspecified"))
      (node (ref "U20") (pin "7") (pinfunction "AOUT2_7") (pintype "unspecified"))
    )
    (net (code "106") (name "Net-(U20-AVREF)") (class "Default")
      (node (ref "RJ4") (pin "2") (pinfunction "2_2") (pintype "unspecified"))
      (node (ref "U20") (pin "12") (pinfunction "AVREF_12") (pintype "unspecified"))
      (node (ref "U20") (pin "13") (pinfunction "BVREF_13") (pintype "unspecified"))
    )
    (net (code "107") (name "Net-(U20-BOUT1)") (class "Default")
      (node (ref "P4") (pin "1") (pinfunction "1_1") (pintype "unspecified"))
      (node (ref "U20") (pin "10") (pinfunction "BOUT1_10") (pintype "unspecified"))
    )
    (net (code "108") (name "Net-(U20-BOUT2)") (class "Default")
      (node (ref "P4") (pin "2") (pinfunction "2_2") (pintype "unspecified"))
      (node (ref "U20") (pin "8") (pinfunction "BOUT2_8") (pintype "unspecified"))
    )
    (net (code "109") (name "Net-(U20-CP1)") (class "Default")
      (node (ref "C43") (pin "2") (pinfunction "2_2") (pintype "input"))
      (node (ref "U20") (pin "1") (pinfunction "CP1_1") (pintype "unspecified"))
    )
    (net (code "110") (name "Net-(U20-CP2)") (class "Default")
      (node (ref "C43") (pin "1") (pinfunction "1_1") (pintype "input"))
      (node (ref "U20") (pin "2") (pinfunction "CP2_2") (pintype "unspecified"))
    )
    (net (code "111") (name "Net-(U20-ISENA)") (class "Default")
      (node (ref "R25") (pin "1") (pinfunction "1_1") (pintype "unspecified"))
      (node (ref "U20") (pin "6") (pinfunction "ISENA_6") (pintype "unspecified"))
    )
    (net (code "112") (name "Net-(U20-ISENB)") (class "Default")
      (node (ref "R26") (pin "1") (pinfunction "1_1") (pintype "unspecified"))
      (node (ref "U20") (pin "9") (pinfunction "ISENB_9") (pintype "unspecified"))
    )
    (net (code "113") (name "Net-(U20-MODE0)") (class "Default")
      (node (ref "SW6") (pin "6") (pinfunction "6_6") (pintype "unspecified"))
      (node (ref "U20") (pin "24") (pinfunction "MODE0_24") (pintype "unspecified"))
    )
    (net (code "114") (name "Net-(U20-MODE1)") (class "Default")
      (node (ref "SW6") (pin "5") (pinfunction "5_5") (pintype "unspecified"))
      (node (ref "U20") (pin "25") (pinfunction "MODE1_25") (pintype "unspecified"))
    )
    (net (code "115") (name "Net-(U20-MODE2)") (class "Default")
      (node (ref "SW6") (pin "4") (pinfunction "4_4") (pintype "unspecified"))
      (node (ref "U20") (pin "26") (pinfunction "MODE2_26") (pintype "unspecified"))
    )
    (net (code "116") (name "Net-(U20-V3P3OUT)") (class "Default")
      (node (ref "C44") (pin "2") (pinfunction "2_2") (pintype "input"))
      (node (ref "RJ4") (pin "3") (pinfunction "3_3") (pintype "unspecified"))
      (node (ref "SW6") (pin "1") (pinfunction "1_1") (pintype "unspecified"))
      (node (ref "SW6") (pin "2") (pinfunction "2_2") (pintype "unspecified"))
      (node (ref "SW6") (pin "3") (pinfunction "3_3") (pintype "unspecified"))
      (node (ref "U20") (pin "15") (pinfunction "V3P3OUT_15") (pintype "unspecified"))
      (node (ref "U20") (pin "16") (pinfunction "nRESET_16") (pintype "unspecified"))
      (node (ref "U20") (pin "17") (pinfunction "nSLEEP_17") (pintype "unspecified"))
    )
    (net (code "117") (name "Net-(U20-VCP)") (class "Default")
      (node (ref "C45") (pin "2") (pinfunction "2_2") (pintype "unspecified"))
      (node (ref "U20") (pin "3") (pinfunction "VCP_3") (pintype "unspecified"))
    )
    (net (code "118") (name "unconnected-(SW2-Pad3)") (class "Default")
      (node (ref "SW2") (pin "3") (pinfunction "3_3") (pintype "input"))
    )
    (net (code "119") (name "unconnected-(U1-DECAY-Pad19)") (class "Default")
      (node (ref "U1") (pin "19") (pinfunction "DECAY_19") (pintype "unspecified+no_connect"))
    )
    (net (code "120") (name "unconnected-(U1-NC-Pad23)") (class "Default")
      (node (ref "U1") (pin "23") (pinfunction "NC_23") (pintype "unspecified+no_connect"))
    )
    (net (code "121") (name "unconnected-(U1-nHOME-Pad27)") (class "Default")
      (node (ref "U1") (pin "27") (pinfunction "nHOME_27") (pintype "unspecified+no_connect"))
    )
    (net (code "122") (name "unconnected-(U2-IO3-Pad15)") (class "Default")
      (node (ref "U2") (pin "15") (pinfunction "IO3_15") (pintype "unspecified+no_connect"))
    )
    (net (code "123") (name "unconnected-(U2-IO35-Pad28)") (class "Default")
      (node (ref "U2") (pin "28") (pinfunction "IO35_28") (pintype "unspecified+no_connect"))
    )
    (net (code "124") (name "unconnected-(U2-IO36-Pad29)") (class "Default")
      (node (ref "U2") (pin "29") (pinfunction "IO36_29") (pintype "unspecified+no_connect"))
    )
    (net (code "125") (name "unconnected-(U2-IO37-Pad30)") (class "Default")
      (node (ref "U2") (pin "30") (pinfunction "IO37_30") (pintype "unspecified+no_connect"))
    )
    (net (code "126") (name "unconnected-(U2-IO45-Pad26)") (class "Default")
      (node (ref "U2") (pin "26") (pinfunction "IO45_26") (pintype "unspecified+no_connect"))
    )
    (net (code "127") (name "unconnected-(U2-IO46-Pad16)") (class "Default")
      (node (ref "U2") (pin "16") (pinfunction "IO46_16") (pintype "unspecified+no_connect"))
    )
    (net (code "128") (name "unconnected-(U3-SBU1-PadA8)") (class "Default")
      (node (ref "U3") (pin "A8") (pinfunction "SBU1_A8") (pintype "unspecified+no_connect"))
    )
    (net (code "129") (name "unconnected-(U3-SBU2-PadB8)") (class "Default")
      (node (ref "U3") (pin "B8") (pinfunction "SBU2_B8") (pintype "unspecified+no_connect"))
    )
    (net (code "130") (name "unconnected-(U4-TAB-Pad4)") (class "Default")
      (node (ref "U4") (pin "4") (pinfunction "TAB_4") (pintype "unspecified+no_connect"))
    )
    (net (code "131") (name "unconnected-(U15-DECAY-Pad19)") (class "Default")
      (node (ref "U15") (pin "19") (pinfunction "DECAY_19") (pintype "unspecified+no_connect"))
    )
    (net (code "132") (name "unconnected-(U15-NC-Pad23)") (class "Default")
      (node (ref "U15") (pin "23") (pinfunction "NC_23") (pintype "unspecified+no_connect"))
    )
    (net (code "133") (name "unconnected-(U15-nHOME-Pad27)") (class "Default")
      (node (ref "U15") (pin "27") (pinfunction "nHOME_27") (pintype "unspecified+no_connect"))
    )
    (net (code "134") (name "unconnected-(U19-DECAY-Pad19)") (class "Default")
      (node (ref "U19") (pin "19") (pinfunction "DECAY_19") (pintype "unspecified+no_connect"))
    )
    (net (code "135") (name "unconnected-(U19-NC-Pad23)") (class "Default")
      (node (ref "U19") (pin "23") (pinfunction "NC_23") (pintype "unspecified+no_connect"))
    )
    (net (code "136") (name "unconnected-(U19-nHOME-Pad27)") (class "Default")
      (node (ref "U19") (pin "27") (pinfunction "nHOME_27") (pintype "unspecified+no_connect"))
    )
    (net (code "137") (name "unconnected-(U20-DECAY-Pad19)") (class "Default")
      (node (ref "U20") (pin "19") (pinfunction "DECAY_19") (pintype "unspecified+no_connect"))
    )
    (net (code "138") (name "unconnected-(U20-NC-Pad23)") (class "Default")
      (node (ref "U20") (pin "23") (pinfunction "NC_23") (pintype "unspecified+no_connect"))
    )
    (net (code "139") (name "unconnected-(U20-nHOME-Pad27)") (class "Default")
      (node (ref "U20") (pin "27") (pinfunction "nHOME_27") (pintype "unspecified+no_connect"))
    )
  )
)
